# NIXIE_Display.net
KiCad netlist of a schematic drawn in Altium Designer
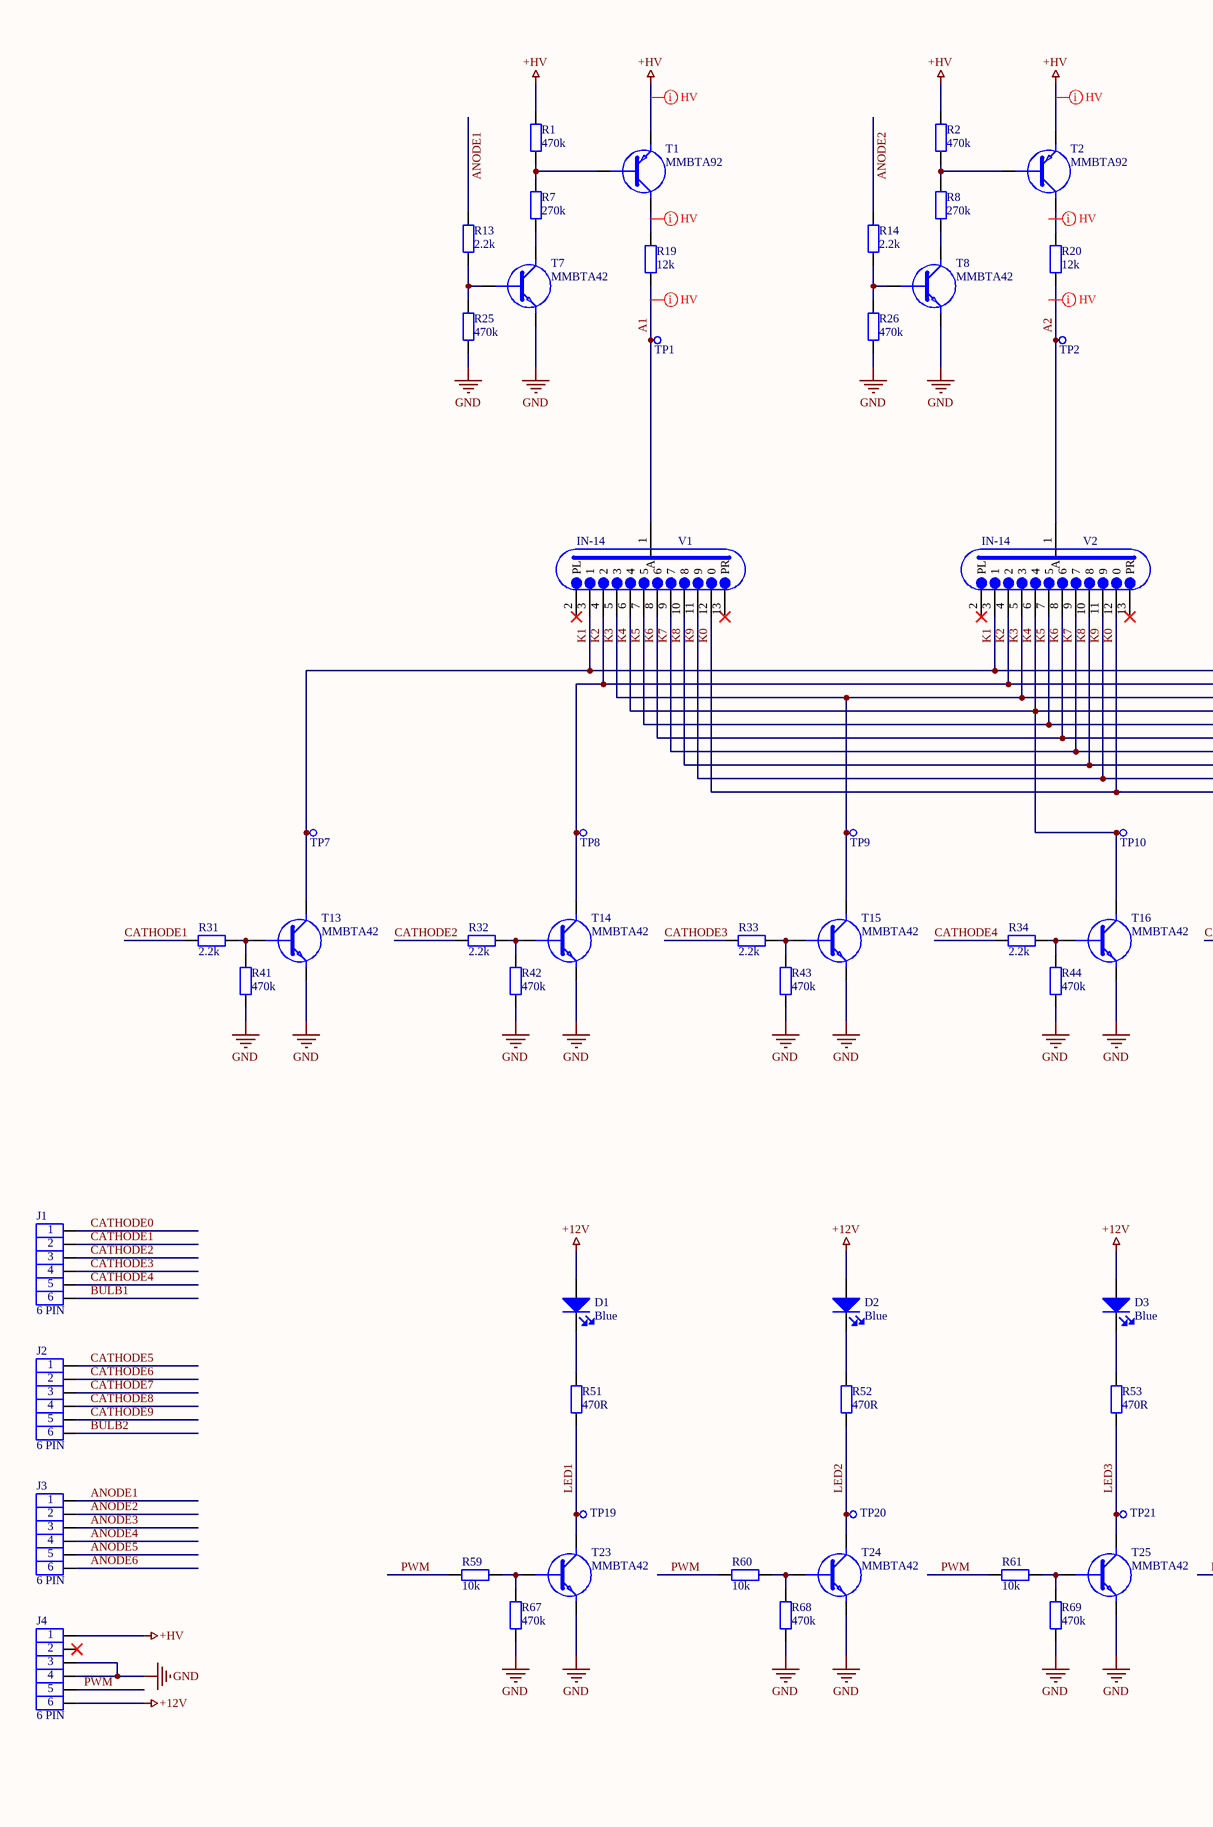
[diagram p0: NIXIE_Display.SchDoc, left]
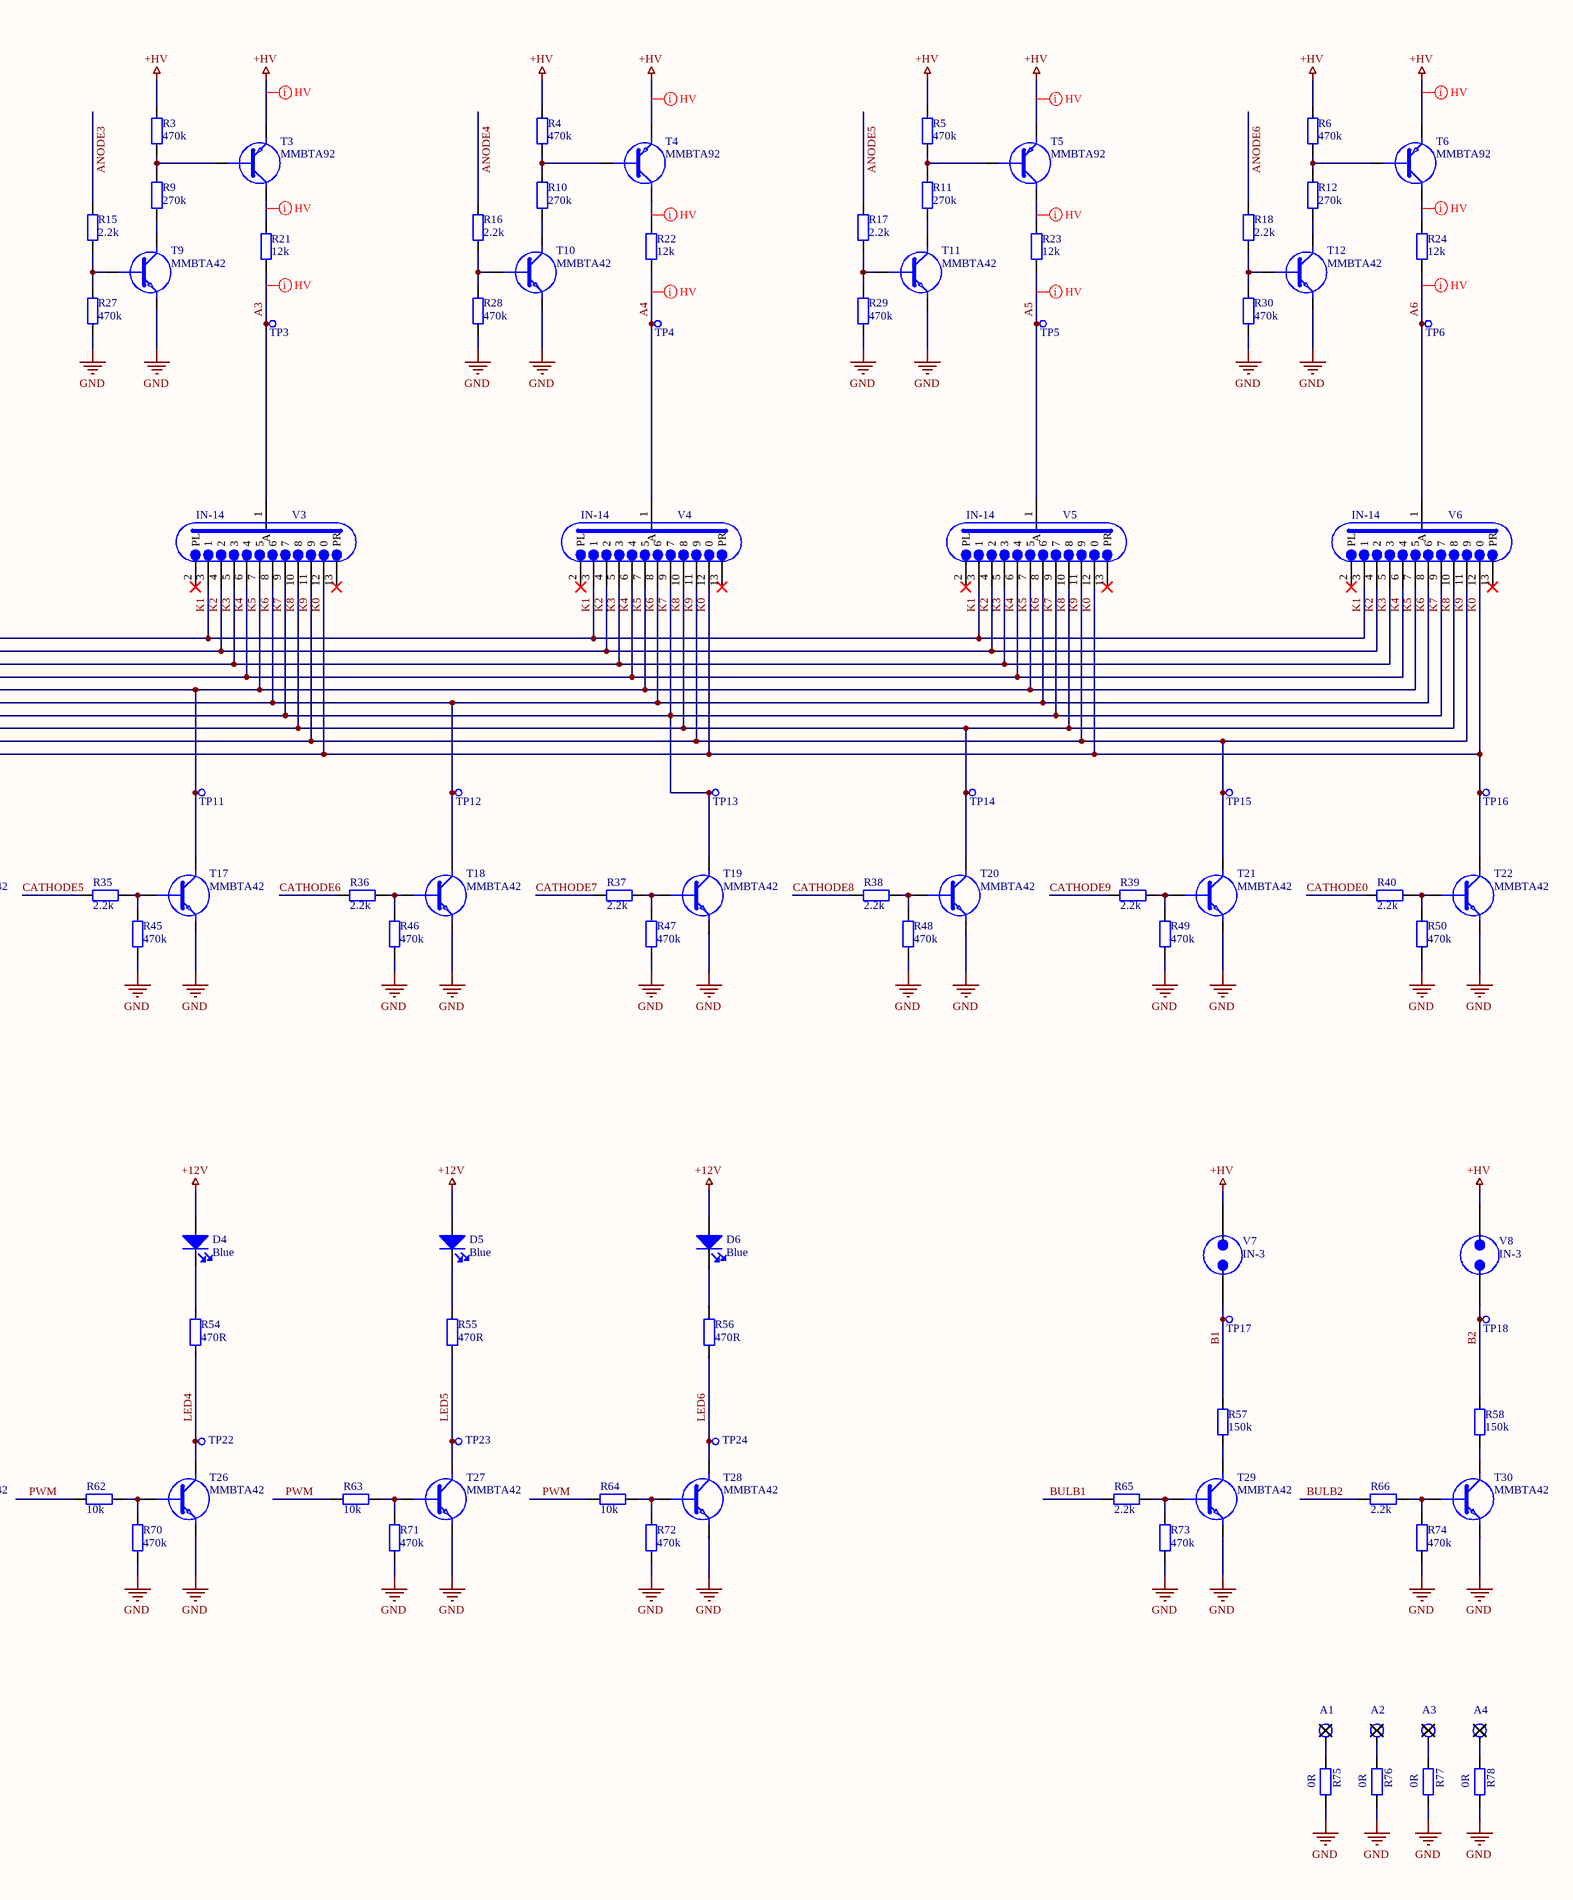
[diagram p1: NIXIE_Display.SchDoc, right]

(export (version "E")
  (design (tool "Eeschema 10.0.6"))
  (components
    (comp (ref "A1")
      (value "3mm")
      (footprint "FOOTPRINTS:HOLE M3")
      (description "Mechanical M3 Hole")
      (libsource (lib "SYMBOLS") (part "Mechanical M3 Hole"))
    )
    (comp (ref "A2")
      (value "3mm")
      (footprint "FOOTPRINTS:HOLE M3")
      (description "Mechanical M3 Hole")
      (libsource (lib "SYMBOLS") (part "Mechanical M3 Hole"))
    )
    (comp (ref "A3")
      (value "3mm")
      (footprint "FOOTPRINTS:HOLE M3")
      (description "Mechanical M3 Hole")
      (libsource (lib "SYMBOLS") (part "Mechanical M3 Hole"))
    )
    (comp (ref "A4")
      (value "3mm")
      (footprint "FOOTPRINTS:HOLE M3")
      (description "Mechanical M3 Hole")
      (libsource (lib "SYMBOLS") (part "Mechanical M3 Hole"))
    )
    (comp (ref "D1")
      (value "Blue")
      (footprint "FOOTPRINTS:LED 0805")
      (description "Standard LEDs - SMD WL-SMCW SMDMono TpVw Waterclr 0805 Blue")
      (fields
        (field (name "MANUFACTURER") "Wurth Elektronik")
        (field (name "MANUFACTURER PART NUMBER") "150080BS75000")
      )
      (libsource (lib "SYMBOLS") (part "Diode LED Blue 0805 SMD 20mA"))
    )
    (comp (ref "D2")
      (value "Blue")
      (footprint "FOOTPRINTS:LED 0805")
      (description "Standard LEDs - SMD WL-SMCW SMDMono TpVw Waterclr 0805 Blue")
      (fields
        (field (name "MANUFACTURER") "Wurth Elektronik")
        (field (name "MANUFACTURER PART NUMBER") "150080BS75000")
      )
      (libsource (lib "SYMBOLS") (part "Diode LED Blue 0805 SMD 20mA"))
    )
    (comp (ref "D3")
      (value "Blue")
      (footprint "FOOTPRINTS:LED 0805")
      (description "Standard LEDs - SMD WL-SMCW SMDMono TpVw Waterclr 0805 Blue")
      (fields
        (field (name "MANUFACTURER") "Wurth Elektronik")
        (field (name "MANUFACTURER PART NUMBER") "150080BS75000")
      )
      (libsource (lib "SYMBOLS") (part "Diode LED Blue 0805 SMD 20mA"))
    )
    (comp (ref "D4")
      (value "Blue")
      (footprint "FOOTPRINTS:LED 0805")
      (description "Standard LEDs - SMD WL-SMCW SMDMono TpVw Waterclr 0805 Blue")
      (fields
        (field (name "MANUFACTURER") "Wurth Elektronik")
        (field (name "MANUFACTURER PART NUMBER") "150080BS75000")
      )
      (libsource (lib "SYMBOLS") (part "Diode LED Blue 0805 SMD 20mA"))
    )
    (comp (ref "D5")
      (value "Blue")
      (footprint "FOOTPRINTS:LED 0805")
      (description "Standard LEDs - SMD WL-SMCW SMDMono TpVw Waterclr 0805 Blue")
      (fields
        (field (name "MANUFACTURER") "Wurth Elektronik")
        (field (name "MANUFACTURER PART NUMBER") "150080BS75000")
      )
      (libsource (lib "SYMBOLS") (part "Diode LED Blue 0805 SMD 20mA"))
    )
    (comp (ref "D6")
      (value "Blue")
      (footprint "FOOTPRINTS:LED 0805")
      (description "Standard LEDs - SMD WL-SMCW SMDMono TpVw Waterclr 0805 Blue")
      (fields
        (field (name "MANUFACTURER") "Wurth Elektronik")
        (field (name "MANUFACTURER PART NUMBER") "150080BS75000")
      )
      (libsource (lib "SYMBOLS") (part "Diode LED Blue 0805 SMD 20mA"))
    )
    (comp (ref "J1")
      (value "6 PIN")
      (footprint "FOOTPRINTS:MECHANICAL PINHEADER 6P 2.54MM MALE")
      (description "Headers & Wire Housings 2.54MM CGRIDIII HDR 6P VERT SR SEL AU")
      (fields (field (name "MANUFACTURER") "Molex") (field (name "MANUFACTURER PART NUMBER") "90120-0766"))
      (libsource (lib "SYMBOLS") (part "Mechanical Pinheader Male 6pin P=2.54mm THT"))
    )
    (comp (ref "J2")
      (value "6 PIN")
      (footprint "FOOTPRINTS:MECHANICAL PINHEADER 6P 2.54MM MALE")
      (description "Headers & Wire Housings 2.54MM CGRIDIII HDR 6P VERT SR SEL AU")
      (fields (field (name "MANUFACTURER") "Molex") (field (name "MANUFACTURER PART NUMBER") "90120-0766"))
      (libsource (lib "SYMBOLS") (part "Mechanical Pinheader Male 6pin P=2.54mm THT"))
    )
    (comp (ref "J3")
      (value "6 PIN")
      (footprint "FOOTPRINTS:MECHANICAL PINHEADER 6P 2.54MM MALE")
      (description "Headers & Wire Housings 2.54MM CGRIDIII HDR 6P VERT SR SEL AU")
      (fields (field (name "MANUFACTURER") "Molex") (field (name "MANUFACTURER PART NUMBER") "90120-0766"))
      (libsource (lib "SYMBOLS") (part "Mechanical Pinheader Male 6pin P=2.54mm THT"))
    )
    (comp (ref "J4")
      (value "6 PIN")
      (footprint "FOOTPRINTS:MECHANICAL PINHEADER 6P 2.54MM MALE")
      (description "Headers & Wire Housings 2.54MM CGRIDIII HDR 6P VERT SR SEL AU")
      (fields (field (name "MANUFACTURER") "Molex") (field (name "MANUFACTURER PART NUMBER") "90120-0766"))
      (libsource (lib "SYMBOLS") (part "Mechanical Pinheader Male 6pin P=2.54mm THT"))
    )
    (comp (ref "R1")
      (value "470k")
      (footprint "FOOTPRINTS:RESISTOR 1206")
      (description "Thin Film Resistors - SMD 1/4W470 kohm 1% 50ppm")
      (fields
        (field (name "MANUFACTURER") "Yageo")
        (field (name "MANUFACTURER PART NUMBER") "RT1206FRE07470KL")
      )
      (libsource (lib "SYMBOLS") (part "Resistor 470k 1% 1/4W 1206"))
    )
    (comp (ref "R2")
      (value "470k")
      (footprint "FOOTPRINTS:RESISTOR 1206")
      (description "Thin Film Resistors - SMD 1/4W470 kohm 1% 50ppm")
      (fields
        (field (name "MANUFACTURER") "Yageo")
        (field (name "MANUFACTURER PART NUMBER") "RT1206FRE07470KL")
      )
      (libsource (lib "SYMBOLS") (part "Resistor 470k 1% 1/4W 1206"))
    )
    (comp (ref "R3")
      (value "470k")
      (footprint "FOOTPRINTS:RESISTOR 1206")
      (description "Thin Film Resistors - SMD 1/4W470 kohm 1% 50ppm")
      (fields
        (field (name "MANUFACTURER") "Yageo")
        (field (name "MANUFACTURER PART NUMBER") "RT1206FRE07470KL")
      )
      (libsource (lib "SYMBOLS") (part "Resistor 470k 1% 1/4W 1206"))
    )
    (comp (ref "R4")
      (value "470k")
      (footprint "FOOTPRINTS:RESISTOR 1206")
      (description "Thin Film Resistors - SMD 1/4W470 kohm 1% 50ppm")
      (fields
        (field (name "MANUFACTURER") "Yageo")
        (field (name "MANUFACTURER PART NUMBER") "RT1206FRE07470KL")
      )
      (libsource (lib "SYMBOLS") (part "Resistor 470k 1% 1/4W 1206"))
    )
    (comp (ref "R5")
      (value "470k")
      (footprint "FOOTPRINTS:RESISTOR 1206")
      (description "Thin Film Resistors - SMD 1/4W470 kohm 1% 50ppm")
      (fields
        (field (name "MANUFACTURER") "Yageo")
        (field (name "MANUFACTURER PART NUMBER") "RT1206FRE07470KL")
      )
      (libsource (lib "SYMBOLS") (part "Resistor 470k 1% 1/4W 1206"))
    )
    (comp (ref "R6")
      (value "470k")
      (footprint "FOOTPRINTS:RESISTOR 1206")
      (description "Thin Film Resistors - SMD 1/4W470 kohm 1% 50ppm")
      (fields
        (field (name "MANUFACTURER") "Yageo")
        (field (name "MANUFACTURER PART NUMBER") "RT1206FRE07470KL")
      )
      (libsource (lib "SYMBOLS") (part "Resistor 470k 1% 1/4W 1206"))
    )
    (comp (ref "R7")
      (value "270k")
      (footprint "FOOTPRINTS:RESISTOR 1206")
      (description "Thin Film Resistors - SMD 1/4W 270 kohm 1% 50ppm")
      (fields
        (field (name "MANUFACTURER") "Yageo")
        (field (name "MANUFACTURER PART NUMBER") "RT1206FRE07270KL")
      )
      (libsource (lib "SYMBOLS") (part "Resistor 270k 1% 1/4W 1206"))
    )
    (comp (ref "R8")
      (value "270k")
      (footprint "FOOTPRINTS:RESISTOR 1206")
      (description "Thin Film Resistors - SMD 1/4W 270 kohm 1% 50ppm")
      (fields
        (field (name "MANUFACTURER") "Yageo")
        (field (name "MANUFACTURER PART NUMBER") "RT1206FRE07270KL")
      )
      (libsource (lib "SYMBOLS") (part "Resistor 270k 1% 1/4W 1206"))
    )
    (comp (ref "R9")
      (value "270k")
      (footprint "FOOTPRINTS:RESISTOR 1206")
      (description "Thin Film Resistors - SMD 1/4W 270 kohm 1% 50ppm")
      (fields
        (field (name "MANUFACTURER") "Yageo")
        (field (name "MANUFACTURER PART NUMBER") "RT1206FRE07270KL")
      )
      (libsource (lib "SYMBOLS") (part "Resistor 270k 1% 1/4W 1206"))
    )
    (comp (ref "R10")
      (value "270k")
      (footprint "FOOTPRINTS:RESISTOR 1206")
      (description "Thin Film Resistors - SMD 1/4W 270 kohm 1% 50ppm")
      (fields
        (field (name "MANUFACTURER") "Yageo")
        (field (name "MANUFACTURER PART NUMBER") "RT1206FRE07270KL")
      )
      (libsource (lib "SYMBOLS") (part "Resistor 270k 1% 1/4W 1206"))
    )
    (comp (ref "R11")
      (value "270k")
      (footprint "FOOTPRINTS:RESISTOR 1206")
      (description "Thin Film Resistors - SMD 1/4W 270 kohm 1% 50ppm")
      (fields
        (field (name "MANUFACTURER") "Yageo")
        (field (name "MANUFACTURER PART NUMBER") "RT1206FRE07270KL")
      )
      (libsource (lib "SYMBOLS") (part "Resistor 270k 1% 1/4W 1206"))
    )
    (comp (ref "R12")
      (value "270k")
      (footprint "FOOTPRINTS:RESISTOR 1206")
      (description "Thin Film Resistors - SMD 1/4W 270 kohm 1% 50ppm")
      (fields
        (field (name "MANUFACTURER") "Yageo")
        (field (name "MANUFACTURER PART NUMBER") "RT1206FRE07270KL")
      )
      (libsource (lib "SYMBOLS") (part "Resistor 270k 1% 1/4W 1206"))
    )
    (comp (ref "R13")
      (value "2.2k")
      (footprint "FOOTPRINTS:RESISTOR 0603")
      (description "Thin Film Resistors - SMD 1/10W 2.2K ohm 1% 50ppm")
      (fields
        (field (name "MANUFACTURER") "Yageo")
        (field (name "MANUFACTURER PART NUMBER") "RT0603FRE072K2L")
      )
      (libsource (lib "SYMBOLS") (part "Resistor 2.2k 1% 1/10W 0603"))
    )
    (comp (ref "R14")
      (value "2.2k")
      (footprint "FOOTPRINTS:RESISTOR 0603")
      (description "Thin Film Resistors - SMD 1/10W 2.2K ohm 1% 50ppm")
      (fields
        (field (name "MANUFACTURER") "Yageo")
        (field (name "MANUFACTURER PART NUMBER") "RT0603FRE072K2L")
      )
      (libsource (lib "SYMBOLS") (part "Resistor 2.2k 1% 1/10W 0603"))
    )
    (comp (ref "R15")
      (value "2.2k")
      (footprint "FOOTPRINTS:RESISTOR 0603")
      (description "Thin Film Resistors - SMD 1/10W 2.2K ohm 1% 50ppm")
      (fields
        (field (name "MANUFACTURER") "Yageo")
        (field (name "MANUFACTURER PART NUMBER") "RT0603FRE072K2L")
      )
      (libsource (lib "SYMBOLS") (part "Resistor 2.2k 1% 1/10W 0603"))
    )
    (comp (ref "R16")
      (value "2.2k")
      (footprint "FOOTPRINTS:RESISTOR 0603")
      (description "Thin Film Resistors - SMD 1/10W 2.2K ohm 1% 50ppm")
      (fields
        (field (name "MANUFACTURER") "Yageo")
        (field (name "MANUFACTURER PART NUMBER") "RT0603FRE072K2L")
      )
      (libsource (lib "SYMBOLS") (part "Resistor 2.2k 1% 1/10W 0603"))
    )
    (comp (ref "R17")
      (value "2.2k")
      (footprint "FOOTPRINTS:RESISTOR 0603")
      (description "Thin Film Resistors - SMD 1/10W 2.2K ohm 1% 50ppm")
      (fields
        (field (name "MANUFACTURER") "Yageo")
        (field (name "MANUFACTURER PART NUMBER") "RT0603FRE072K2L")
      )
      (libsource (lib "SYMBOLS") (part "Resistor 2.2k 1% 1/10W 0603"))
    )
    (comp (ref "R18")
      (value "2.2k")
      (footprint "FOOTPRINTS:RESISTOR 0603")
      (description "Thin Film Resistors - SMD 1/10W 2.2K ohm 1% 50ppm")
      (fields
        (field (name "MANUFACTURER") "Yageo")
        (field (name "MANUFACTURER PART NUMBER") "RT0603FRE072K2L")
      )
      (libsource (lib "SYMBOLS") (part "Resistor 2.2k 1% 1/10W 0603"))
    )
    (comp (ref "R19")
      (value "12k")
      (footprint "FOOTPRINTS:RESISTOR 0603")
      (description "Thin Film Resistors - SMD 1/10W 12K ohm 1% 50ppm")
      (fields
        (field (name "MANUFACTURER") "Yageo")
        (field (name "MANUFACTURER PART NUMBER") "RT0603FRE1312KL")
      )
      (libsource (lib "SYMBOLS") (part "Resistor 12k 1% 1/10W 0603"))
    )
    (comp (ref "R20")
      (value "12k")
      (footprint "FOOTPRINTS:RESISTOR 0603")
      (description "Thin Film Resistors - SMD 1/10W 12K ohm 1% 50ppm")
      (fields
        (field (name "MANUFACTURER") "Yageo")
        (field (name "MANUFACTURER PART NUMBER") "RT0603FRE1312KL")
      )
      (libsource (lib "SYMBOLS") (part "Resistor 12k 1% 1/10W 0603"))
    )
    (comp (ref "R21")
      (value "12k")
      (footprint "FOOTPRINTS:RESISTOR 0603")
      (description "Thin Film Resistors - SMD 1/10W 12K ohm 1% 50ppm")
      (fields
        (field (name "MANUFACTURER") "Yageo")
        (field (name "MANUFACTURER PART NUMBER") "RT0603FRE1312KL")
      )
      (libsource (lib "SYMBOLS") (part "Resistor 12k 1% 1/10W 0603"))
    )
    (comp (ref "R22")
      (value "12k")
      (footprint "FOOTPRINTS:RESISTOR 0603")
      (description "Thin Film Resistors - SMD 1/10W 12K ohm 1% 50ppm")
      (fields
        (field (name "MANUFACTURER") "Yageo")
        (field (name "MANUFACTURER PART NUMBER") "RT0603FRE1312KL")
      )
      (libsource (lib "SYMBOLS") (part "Resistor 12k 1% 1/10W 0603"))
    )
    (comp (ref "R23")
      (value "12k")
      (footprint "FOOTPRINTS:RESISTOR 0603")
      (description "Thin Film Resistors - SMD 1/10W 12K ohm 1% 50ppm")
      (fields
        (field (name "MANUFACTURER") "Yageo")
        (field (name "MANUFACTURER PART NUMBER") "RT0603FRE1312KL")
      )
      (libsource (lib "SYMBOLS") (part "Resistor 12k 1% 1/10W 0603"))
    )
    (comp (ref "R24")
      (value "12k")
      (footprint "FOOTPRINTS:RESISTOR 0603")
      (description "Thin Film Resistors - SMD 1/10W 12K ohm 1% 50ppm")
      (fields
        (field (name "MANUFACTURER") "Yageo")
        (field (name "MANUFACTURER PART NUMBER") "RT0603FRE1312KL")
      )
      (libsource (lib "SYMBOLS") (part "Resistor 12k 1% 1/10W 0603"))
    )
    (comp (ref "R25")
      (value "470k")
      (footprint "FOOTPRINTS:RESISTOR 0603")
      (description "Thin Film Resistors - SMD 1/10W 470K ohm 1% 50ppm")
      (fields
        (field (name "MANUFACTURER") "Yageo")
        (field (name "MANUFACTURER PART NUMBER") "RT0603FRE13470KL")
      )
      (libsource (lib "SYMBOLS") (part "Resistor 470k 1% 1/10W 0603"))
    )
    (comp (ref "R26")
      (value "470k")
      (footprint "FOOTPRINTS:RESISTOR 0603")
      (description "Thin Film Resistors - SMD 1/10W 470K ohm 1% 50ppm")
      (fields
        (field (name "MANUFACTURER") "Yageo")
        (field (name "MANUFACTURER PART NUMBER") "RT0603FRE13470KL")
      )
      (libsource (lib "SYMBOLS") (part "Resistor 470k 1% 1/10W 0603"))
    )
    (comp (ref "R27")
      (value "470k")
      (footprint "FOOTPRINTS:RESISTOR 0603")
      (description "Thin Film Resistors - SMD 1/10W 470K ohm 1% 50ppm")
      (fields
        (field (name "MANUFACTURER") "Yageo")
        (field (name "MANUFACTURER PART NUMBER") "RT0603FRE13470KL")
      )
      (libsource (lib "SYMBOLS") (part "Resistor 470k 1% 1/10W 0603"))
    )
    (comp (ref "R28")
      (value "470k")
      (footprint "FOOTPRINTS:RESISTOR 0603")
      (description "Thin Film Resistors - SMD 1/10W 470K ohm 1% 50ppm")
      (fields
        (field (name "MANUFACTURER") "Yageo")
        (field (name "MANUFACTURER PART NUMBER") "RT0603FRE13470KL")
      )
      (libsource (lib "SYMBOLS") (part "Resistor 470k 1% 1/10W 0603"))
    )
    (comp (ref "R29")
      (value "470k")
      (footprint "FOOTPRINTS:RESISTOR 0603")
      (description "Thin Film Resistors - SMD 1/10W 470K ohm 1% 50ppm")
      (fields
        (field (name "MANUFACTURER") "Yageo")
        (field (name "MANUFACTURER PART NUMBER") "RT0603FRE13470KL")
      )
      (libsource (lib "SYMBOLS") (part "Resistor 470k 1% 1/10W 0603"))
    )
    (comp (ref "R30")
      (value "470k")
      (footprint "FOOTPRINTS:RESISTOR 0603")
      (description "Thin Film Resistors - SMD 1/10W 470K ohm 1% 50ppm")
      (fields
        (field (name "MANUFACTURER") "Yageo")
        (field (name "MANUFACTURER PART NUMBER") "RT0603FRE13470KL")
      )
      (libsource (lib "SYMBOLS") (part "Resistor 470k 1% 1/10W 0603"))
    )
    (comp (ref "R31")
      (value "2.2k")
      (footprint "FOOTPRINTS:RESISTOR 0603")
      (description "Thin Film Resistors - SMD 1/10W 2.2K ohm 1% 50ppm")
      (fields
        (field (name "MANUFACTURER") "Yageo")
        (field (name "MANUFACTURER PART NUMBER") "RT0603FRE072K2L")
      )
      (libsource (lib "") (part "Resistor 2.2k 1% 1/10W 0603_1"))
    )
    (comp (ref "R32")
      (value "2.2k")
      (footprint "FOOTPRINTS:RESISTOR 0603")
      (description "Thin Film Resistors - SMD 1/10W 2.2K ohm 1% 50ppm")
      (fields
        (field (name "MANUFACTURER") "Yageo")
        (field (name "MANUFACTURER PART NUMBER") "RT0603FRE072K2L")
      )
      (libsource (lib "") (part "Resistor 2.2k 1% 1/10W 0603_1"))
    )
    (comp (ref "R33")
      (value "2.2k")
      (footprint "FOOTPRINTS:RESISTOR 0603")
      (description "Thin Film Resistors - SMD 1/10W 2.2K ohm 1% 50ppm")
      (fields
        (field (name "MANUFACTURER") "Yageo")
        (field (name "MANUFACTURER PART NUMBER") "RT0603FRE072K2L")
      )
      (libsource (lib "") (part "Resistor 2.2k 1% 1/10W 0603_1"))
    )
    (comp (ref "R34")
      (value "2.2k")
      (footprint "FOOTPRINTS:RESISTOR 0603")
      (description "Thin Film Resistors - SMD 1/10W 2.2K ohm 1% 50ppm")
      (fields
        (field (name "MANUFACTURER") "Yageo")
        (field (name "MANUFACTURER PART NUMBER") "RT0603FRE072K2L")
      )
      (libsource (lib "") (part "Resistor 2.2k 1% 1/10W 0603_1"))
    )
    (comp (ref "R35")
      (value "2.2k")
      (footprint "FOOTPRINTS:RESISTOR 0603")
      (description "Thin Film Resistors - SMD 1/10W 2.2K ohm 1% 50ppm")
      (fields
        (field (name "MANUFACTURER") "Yageo")
        (field (name "MANUFACTURER PART NUMBER") "RT0603FRE072K2L")
      )
      (libsource (lib "") (part "Resistor 2.2k 1% 1/10W 0603_1"))
    )
    (comp (ref "R36")
      (value "2.2k")
      (footprint "FOOTPRINTS:RESISTOR 0603")
      (description "Thin Film Resistors - SMD 1/10W 2.2K ohm 1% 50ppm")
      (fields
        (field (name "MANUFACTURER") "Yageo")
        (field (name "MANUFACTURER PART NUMBER") "RT0603FRE072K2L")
      )
      (libsource (lib "") (part "Resistor 2.2k 1% 1/10W 0603_1"))
    )
    (comp (ref "R37")
      (value "2.2k")
      (footprint "FOOTPRINTS:RESISTOR 0603")
      (description "Thin Film Resistors - SMD 1/10W 2.2K ohm 1% 50ppm")
      (fields
        (field (name "MANUFACTURER") "Yageo")
        (field (name "MANUFACTURER PART NUMBER") "RT0603FRE072K2L")
      )
      (libsource (lib "") (part "Resistor 2.2k 1% 1/10W 0603_1"))
    )
    (comp (ref "R38")
      (value "2.2k")
      (footprint "FOOTPRINTS:RESISTOR 0603")
      (description "Thin Film Resistors - SMD 1/10W 2.2K ohm 1% 50ppm")
      (fields
        (field (name "MANUFACTURER") "Yageo")
        (field (name "MANUFACTURER PART NUMBER") "RT0603FRE072K2L")
      )
      (libsource (lib "") (part "Resistor 2.2k 1% 1/10W 0603_1"))
    )
    (comp (ref "R39")
      (value "2.2k")
      (footprint "FOOTPRINTS:RESISTOR 0603")
      (description "Thin Film Resistors - SMD 1/10W 2.2K ohm 1% 50ppm")
      (fields
        (field (name "MANUFACTURER") "Yageo")
        (field (name "MANUFACTURER PART NUMBER") "RT0603FRE072K2L")
      )
      (libsource (lib "") (part "Resistor 2.2k 1% 1/10W 0603_1"))
    )
    (comp (ref "R40")
      (value "2.2k")
      (footprint "FOOTPRINTS:RESISTOR 0603")
      (description "Thin Film Resistors - SMD 1/10W 2.2K ohm 1% 50ppm")
      (fields
        (field (name "MANUFACTURER") "Yageo")
        (field (name "MANUFACTURER PART NUMBER") "RT0603FRE072K2L")
      )
      (libsource (lib "") (part "Resistor 2.2k 1% 1/10W 0603_1"))
    )
    (comp (ref "R41")
      (value "470k")
      (footprint "FOOTPRINTS:RESISTOR 0603")
      (description "Thin Film Resistors - SMD 1/10W 470K ohm 1% 50ppm")
      (fields
        (field (name "MANUFACTURER") "Yageo")
        (field (name "MANUFACTURER PART NUMBER") "RT0603FRE13470KL")
      )
      (libsource (lib "SYMBOLS") (part "Resistor 470k 1% 1/10W 0603"))
    )
    (comp (ref "R42")
      (value "470k")
      (footprint "FOOTPRINTS:RESISTOR 0603")
      (description "Thin Film Resistors - SMD 1/10W 470K ohm 1% 50ppm")
      (fields
        (field (name "MANUFACTURER") "Yageo")
        (field (name "MANUFACTURER PART NUMBER") "RT0603FRE13470KL")
      )
      (libsource (lib "SYMBOLS") (part "Resistor 470k 1% 1/10W 0603"))
    )
    (comp (ref "R43")
      (value "470k")
      (footprint "FOOTPRINTS:RESISTOR 0603")
      (description "Thin Film Resistors - SMD 1/10W 470K ohm 1% 50ppm")
      (fields
        (field (name "MANUFACTURER") "Yageo")
        (field (name "MANUFACTURER PART NUMBER") "RT0603FRE13470KL")
      )
      (libsource (lib "SYMBOLS") (part "Resistor 470k 1% 1/10W 0603"))
    )
    (comp (ref "R44")
      (value "470k")
      (footprint "FOOTPRINTS:RESISTOR 0603")
      (description "Thin Film Resistors - SMD 1/10W 470K ohm 1% 50ppm")
      (fields
        (field (name "MANUFACTURER") "Yageo")
        (field (name "MANUFACTURER PART NUMBER") "RT0603FRE13470KL")
      )
      (libsource (lib "SYMBOLS") (part "Resistor 470k 1% 1/10W 0603"))
    )
    (comp (ref "R45")
      (value "470k")
      (footprint "FOOTPRINTS:RESISTOR 0603")
      (description "Thin Film Resistors - SMD 1/10W 470K ohm 1% 50ppm")
      (fields
        (field (name "MANUFACTURER") "Yageo")
        (field (name "MANUFACTURER PART NUMBER") "RT0603FRE13470KL")
      )
      (libsource (lib "SYMBOLS") (part "Resistor 470k 1% 1/10W 0603"))
    )
    (comp (ref "R46")
      (value "470k")
      (footprint "FOOTPRINTS:RESISTOR 0603")
      (description "Thin Film Resistors - SMD 1/10W 470K ohm 1% 50ppm")
      (fields
        (field (name "MANUFACTURER") "Yageo")
        (field (name "MANUFACTURER PART NUMBER") "RT0603FRE13470KL")
      )
      (libsource (lib "SYMBOLS") (part "Resistor 470k 1% 1/10W 0603"))
    )
    (comp (ref "R47")
      (value "470k")
      (footprint "FOOTPRINTS:RESISTOR 0603")
      (description "Thin Film Resistors - SMD 1/10W 470K ohm 1% 50ppm")
      (fields
        (field (name "MANUFACTURER") "Yageo")
        (field (name "MANUFACTURER PART NUMBER") "RT0603FRE13470KL")
      )
      (libsource (lib "SYMBOLS") (part "Resistor 470k 1% 1/10W 0603"))
    )
    (comp (ref "R48")
      (value "470k")
      (footprint "FOOTPRINTS:RESISTOR 0603")
      (description "Thin Film Resistors - SMD 1/10W 470K ohm 1% 50ppm")
      (fields
        (field (name "MANUFACTURER") "Yageo")
        (field (name "MANUFACTURER PART NUMBER") "RT0603FRE13470KL")
      )
      (libsource (lib "SYMBOLS") (part "Resistor 470k 1% 1/10W 0603"))
    )
    (comp (ref "R49")
      (value "470k")
      (footprint "FOOTPRINTS:RESISTOR 0603")
      (description "Thin Film Resistors - SMD 1/10W 470K ohm 1% 50ppm")
      (fields
        (field (name "MANUFACTURER") "Yageo")
        (field (name "MANUFACTURER PART NUMBER") "RT0603FRE13470KL")
      )
      (libsource (lib "SYMBOLS") (part "Resistor 470k 1% 1/10W 0603"))
    )
    (comp (ref "R50")
      (value "470k")
      (footprint "FOOTPRINTS:RESISTOR 0603")
      (description "Thin Film Resistors - SMD 1/10W 470K ohm 1% 50ppm")
      (fields
        (field (name "MANUFACTURER") "Yageo")
        (field (name "MANUFACTURER PART NUMBER") "RT0603FRE13470KL")
      )
      (libsource (lib "SYMBOLS") (part "Resistor 470k 1% 1/10W 0603"))
    )
    (comp (ref "R51")
      (value "470R")
      (footprint "FOOTPRINTS:RESISTOR 0603")
      (description "Thin Film Resistors - SMD 1/10W 470R ohm 1% 50ppm")
      (fields
        (field (name "MANUFACTURER") "Yageo")
        (field (name "MANUFACTURER PART NUMBER") "RT0603FRE07470RL")
      )
      (libsource (lib "SYMBOLS") (part "Resistor 470R 1% 1/10W 0603"))
    )
    (comp (ref "R52")
      (value "470R")
      (footprint "FOOTPRINTS:RESISTOR 0603")
      (description "Thin Film Resistors - SMD 1/10W 470R ohm 1% 50ppm")
      (fields
        (field (name "MANUFACTURER") "Yageo")
        (field (name "MANUFACTURER PART NUMBER") "RT0603FRE07470RL")
      )
      (libsource (lib "SYMBOLS") (part "Resistor 470R 1% 1/10W 0603"))
    )
    (comp (ref "R53")
      (value "470R")
      (footprint "FOOTPRINTS:RESISTOR 0603")
      (description "Thin Film Resistors - SMD 1/10W 470R ohm 1% 50ppm")
      (fields
        (field (name "MANUFACTURER") "Yageo")
        (field (name "MANUFACTURER PART NUMBER") "RT0603FRE07470RL")
      )
      (libsource (lib "SYMBOLS") (part "Resistor 470R 1% 1/10W 0603"))
    )
    (comp (ref "R54")
      (value "470R")
      (footprint "FOOTPRINTS:RESISTOR 0603")
      (description "Thin Film Resistors - SMD 1/10W 470R ohm 1% 50ppm")
      (fields
        (field (name "MANUFACTURER") "Yageo")
        (field (name "MANUFACTURER PART NUMBER") "RT0603FRE07470RL")
      )
      (libsource (lib "SYMBOLS") (part "Resistor 470R 1% 1/10W 0603"))
    )
    (comp (ref "R55")
      (value "470R")
      (footprint "FOOTPRINTS:RESISTOR 0603")
      (description "Thin Film Resistors - SMD 1/10W 470R ohm 1% 50ppm")
      (fields
        (field (name "MANUFACTURER") "Yageo")
        (field (name "MANUFACTURER PART NUMBER") "RT0603FRE07470RL")
      )
      (libsource (lib "SYMBOLS") (part "Resistor 470R 1% 1/10W 0603"))
    )
    (comp (ref "R56")
      (value "470R")
      (footprint "FOOTPRINTS:RESISTOR 0603")
      (description "Thin Film Resistors - SMD 1/10W 470R ohm 1% 50ppm")
      (fields
        (field (name "MANUFACTURER") "Yageo")
        (field (name "MANUFACTURER PART NUMBER") "RT0603FRE07470RL")
      )
      (libsource (lib "SYMBOLS") (part "Resistor 470R 1% 1/10W 0603"))
    )
    (comp (ref "R57")
      (value "150k")
      (footprint "FOOTPRINTS:RESISTOR 0603")
      (description "Thin Film Resistors - SMD 1/10W 150K ohm 1% 50ppm")
      (fields
        (field (name "MANUFACTURER") "Yageo")
        (field (name "MANUFACTURER PART NUMBER") "RT0603FRE13150KL")
      )
      (libsource (lib "SYMBOLS") (part "Resistor 150k 1% 1/10W 0603"))
    )
    (comp (ref "R58")
      (value "150k")
      (footprint "FOOTPRINTS:RESISTOR 0603")
      (description "Thin Film Resistors - SMD 1/10W 150K ohm 1% 50ppm")
      (fields
        (field (name "MANUFACTURER") "Yageo")
        (field (name "MANUFACTURER PART NUMBER") "RT0603FRE13150KL")
      )
      (libsource (lib "SYMBOLS") (part "Resistor 150k 1% 1/10W 0603"))
    )
    (comp (ref "R59")
      (value "10k")
      (footprint "FOOTPRINTS:RESISTOR 0603")
      (description "Thin Film Resistors - SMD 1/10W 10K ohm 1% 50ppm")
      (fields
        (field (name "MANUFACTURER") "Yageo")
        (field (name "MANUFACTURER PART NUMBER") "RT0603FRE1310KL")
      )
      (libsource (lib "SYMBOLS") (part "Resistor 10k 1% 1/10W 0603"))
    )
    (comp (ref "R60")
      (value "10k")
      (footprint "FOOTPRINTS:RESISTOR 0603")
      (description "Thin Film Resistors - SMD 1/10W 10K ohm 1% 50ppm")
      (fields
        (field (name "MANUFACTURER") "Yageo")
        (field (name "MANUFACTURER PART NUMBER") "RT0603FRE1310KL")
      )
      (libsource (lib "SYMBOLS") (part "Resistor 10k 1% 1/10W 0603"))
    )
    (comp (ref "R61")
      (value "10k")
      (footprint "FOOTPRINTS:RESISTOR 0603")
      (description "Thin Film Resistors - SMD 1/10W 10K ohm 1% 50ppm")
      (fields
        (field (name "MANUFACTURER") "Yageo")
        (field (name "MANUFACTURER PART NUMBER") "RT0603FRE1310KL")
      )
      (libsource (lib "SYMBOLS") (part "Resistor 10k 1% 1/10W 0603"))
    )
    (comp (ref "R62")
      (value "10k")
      (footprint "FOOTPRINTS:RESISTOR 0603")
      (description "Thin Film Resistors - SMD 1/10W 10K ohm 1% 50ppm")
      (fields
        (field (name "MANUFACTURER") "Yageo")
        (field (name "MANUFACTURER PART NUMBER") "RT0603FRE1310KL")
      )
      (libsource (lib "SYMBOLS") (part "Resistor 10k 1% 1/10W 0603"))
    )
    (comp (ref "R63")
      (value "10k")
      (footprint "FOOTPRINTS:RESISTOR 0603")
      (description "Thin Film Resistors - SMD 1/10W 10K ohm 1% 50ppm")
      (fields
        (field (name "MANUFACTURER") "Yageo")
        (field (name "MANUFACTURER PART NUMBER") "RT0603FRE1310KL")
      )
      (libsource (lib "SYMBOLS") (part "Resistor 10k 1% 1/10W 0603"))
    )
    (comp (ref "R64")
      (value "10k")
      (footprint "FOOTPRINTS:RESISTOR 0603")
      (description "Thin Film Resistors - SMD 1/10W 10K ohm 1% 50ppm")
      (fields
        (field (name "MANUFACTURER") "Yageo")
        (field (name "MANUFACTURER PART NUMBER") "RT0603FRE1310KL")
      )
      (libsource (lib "SYMBOLS") (part "Resistor 10k 1% 1/10W 0603"))
    )
    (comp (ref "R65")
      (value "2.2k")
      (footprint "FOOTPRINTS:RESISTOR 0603")
      (description "Thin Film Resistors - SMD 1/10W 2.2K ohm 1% 50ppm")
      (fields
        (field (name "MANUFACTURER") "Yageo")
        (field (name "MANUFACTURER PART NUMBER") "RT0603FRE072K2L")
      )
      (libsource (lib "") (part "Resistor 2.2k 1% 1/10W 0603_1"))
    )
    (comp (ref "R66")
      (value "2.2k")
      (footprint "FOOTPRINTS:RESISTOR 0603")
      (description "Thin Film Resistors - SMD 1/10W 2.2K ohm 1% 50ppm")
      (fields
        (field (name "MANUFACTURER") "Yageo")
        (field (name "MANUFACTURER PART NUMBER") "RT0603FRE072K2L")
      )
      (libsource (lib "") (part "Resistor 2.2k 1% 1/10W 0603_1"))
    )
    (comp (ref "R67")
      (value "470k")
      (footprint "FOOTPRINTS:RESISTOR 0603")
      (description "Thin Film Resistors - SMD 1/10W 470K ohm 1% 50ppm")
      (fields
        (field (name "MANUFACTURER") "Yageo")
        (field (name "MANUFACTURER PART NUMBER") "RT0603FRE13470KL")
      )
      (libsource (lib "SYMBOLS") (part "Resistor 470k 1% 1/10W 0603"))
    )
    (comp (ref "R68")
      (value "470k")
      (footprint "FOOTPRINTS:RESISTOR 0603")
      (description "Thin Film Resistors - SMD 1/10W 470K ohm 1% 50ppm")
      (fields
        (field (name "MANUFACTURER") "Yageo")
        (field (name "MANUFACTURER PART NUMBER") "RT0603FRE13470KL")
      )
      (libsource (lib "SYMBOLS") (part "Resistor 470k 1% 1/10W 0603"))
    )
    (comp (ref "R69")
      (value "470k")
      (footprint "FOOTPRINTS:RESISTOR 0603")
      (description "Thin Film Resistors - SMD 1/10W 470K ohm 1% 50ppm")
      (fields
        (field (name "MANUFACTURER") "Yageo")
        (field (name "MANUFACTURER PART NUMBER") "RT0603FRE13470KL")
      )
      (libsource (lib "SYMBOLS") (part "Resistor 470k 1% 1/10W 0603"))
    )
    (comp (ref "R70")
      (value "470k")
      (footprint "FOOTPRINTS:RESISTOR 0603")
      (description "Thin Film Resistors - SMD 1/10W 470K ohm 1% 50ppm")
      (fields
        (field (name "MANUFACTURER") "Yageo")
        (field (name "MANUFACTURER PART NUMBER") "RT0603FRE13470KL")
      )
      (libsource (lib "SYMBOLS") (part "Resistor 470k 1% 1/10W 0603"))
    )
    (comp (ref "R71")
      (value "470k")
      (footprint "FOOTPRINTS:RESISTOR 0603")
      (description "Thin Film Resistors - SMD 1/10W 470K ohm 1% 50ppm")
      (fields
        (field (name "MANUFACTURER") "Yageo")
        (field (name "MANUFACTURER PART NUMBER") "RT0603FRE13470KL")
      )
      (libsource (lib "SYMBOLS") (part "Resistor 470k 1% 1/10W 0603"))
    )
    (comp (ref "R72")
      (value "470k")
      (footprint "FOOTPRINTS:RESISTOR 0603")
      (description "Thin Film Resistors - SMD 1/10W 470K ohm 1% 50ppm")
      (fields
        (field (name "MANUFACTURER") "Yageo")
        (field (name "MANUFACTURER PART NUMBER") "RT0603FRE13470KL")
      )
      (libsource (lib "SYMBOLS") (part "Resistor 470k 1% 1/10W 0603"))
    )
    (comp (ref "R73")
      (value "470k")
      (footprint "FOOTPRINTS:RESISTOR 0603")
      (description "Thin Film Resistors - SMD 1/10W 470K ohm 1% 50ppm")
      (fields
        (field (name "MANUFACTURER") "Yageo")
        (field (name "MANUFACTURER PART NUMBER") "RT0603FRE13470KL")
      )
      (libsource (lib "SYMBOLS") (part "Resistor 470k 1% 1/10W 0603"))
    )
    (comp (ref "R74")
      (value "470k")
      (footprint "FOOTPRINTS:RESISTOR 0603")
      (description "Thin Film Resistors - SMD 1/10W 470K ohm 1% 50ppm")
      (fields
        (field (name "MANUFACTURER") "Yageo")
        (field (name "MANUFACTURER PART NUMBER") "RT0603FRE13470KL")
      )
      (libsource (lib "SYMBOLS") (part "Resistor 470k 1% 1/10W 0603"))
    )
    (comp (ref "R75")
      (value "0R")
      (footprint "FOOTPRINTS:RESISTOR 0603")
      (description "Thick Film Resistors - SMD 0 Ohms 100 mW 0603 5%")
      (fields
        (field (name "MANUFACTURER") "Yageo")
        (field (name "MANUFACTURER PART NUMBER") "RC0603JR-070RL")
      )
      (libsource (lib "SYMBOLS") (part "Resistor 0R 1% 1/10W 0603"))
    )
    (comp (ref "R76")
      (value "0R")
      (footprint "FOOTPRINTS:RESISTOR 0603")
      (description "Thick Film Resistors - SMD 0 Ohms 100 mW 0603 5%")
      (fields
        (field (name "MANUFACTURER") "Yageo")
        (field (name "MANUFACTURER PART NUMBER") "RC0603JR-070RL")
      )
      (libsource (lib "SYMBOLS") (part "Resistor 0R 1% 1/10W 0603"))
    )
    (comp (ref "R77")
      (value "0R")
      (footprint "FOOTPRINTS:RESISTOR 0603")
      (description "Thick Film Resistors - SMD 0 Ohms 100 mW 0603 5%")
      (fields
        (field (name "MANUFACTURER") "Yageo")
        (field (name "MANUFACTURER PART NUMBER") "RC0603JR-070RL")
      )
      (libsource (lib "SYMBOLS") (part "Resistor 0R 1% 1/10W 0603"))
    )
    (comp (ref "R78")
      (value "0R")
      (footprint "FOOTPRINTS:RESISTOR 0603")
      (description "Thick Film Resistors - SMD 0 Ohms 100 mW 0603 5%")
      (fields
        (field (name "MANUFACTURER") "Yageo")
        (field (name "MANUFACTURER PART NUMBER") "RC0603JR-070RL")
      )
      (libsource (lib "SYMBOLS") (part "Resistor 0R 1% 1/10W 0603"))
    )
    (comp (ref "T1")
      (value "MMBTA92")
      (footprint "FOOTPRINTS:SOT23-3")
      (description "Bipolar Transistors - BJT BJT, SOT-23, 300V, 500mA, PNP")
      (fields
        (field (name "MANUFACTURER PART NUMBER") "MMBTA42")
        (field (name "MANUFACTURER") "Diotec Semiconductor")
      )
      (libsource (lib "SYMBOLS") (part "Transistor PNP 500mA 300V MMBTA92"))
    )
    (comp (ref "T2")
      (value "MMBTA92")
      (footprint "FOOTPRINTS:SOT23-3")
      (description "Bipolar Transistors - BJT BJT, SOT-23, 300V, 500mA, PNP")
      (fields
        (field (name "MANUFACTURER PART NUMBER") "MMBTA42")
        (field (name "MANUFACTURER") "Diotec Semiconductor")
      )
      (libsource (lib "SYMBOLS") (part "Transistor PNP 500mA 300V MMBTA92"))
    )
    (comp (ref "T3")
      (value "MMBTA92")
      (footprint "FOOTPRINTS:SOT23-3")
      (description "Bipolar Transistors - BJT BJT, SOT-23, 300V, 500mA, PNP")
      (fields
        (field (name "MANUFACTURER PART NUMBER") "MMBTA42")
        (field (name "MANUFACTURER") "Diotec Semiconductor")
      )
      (libsource (lib "SYMBOLS") (part "Transistor PNP 500mA 300V MMBTA92"))
    )
    (comp (ref "T4")
      (value "MMBTA92")
      (footprint "FOOTPRINTS:SOT23-3")
      (description "Bipolar Transistors - BJT BJT, SOT-23, 300V, 500mA, PNP")
      (fields
        (field (name "MANUFACTURER PART NUMBER") "MMBTA42")
        (field (name "MANUFACTURER") "Diotec Semiconductor")
      )
      (libsource (lib "SYMBOLS") (part "Transistor PNP 500mA 300V MMBTA92"))
    )
    (comp (ref "T5")
      (value "MMBTA92")
      (footprint "FOOTPRINTS:SOT23-3")
      (description "Bipolar Transistors - BJT BJT, SOT-23, 300V, 500mA, PNP")
      (fields
        (field (name "MANUFACTURER PART NUMBER") "MMBTA42")
        (field (name "MANUFACTURER") "Diotec Semiconductor")
      )
      (libsource (lib "SYMBOLS") (part "Transistor PNP 500mA 300V MMBTA92"))
    )
    (comp (ref "T6")
      (value "MMBTA92")
      (footprint "FOOTPRINTS:SOT23-3")
      (description "Bipolar Transistors - BJT BJT, SOT-23, 300V, 500mA, PNP")
      (fields
        (field (name "MANUFACTURER PART NUMBER") "MMBTA42")
        (field (name "MANUFACTURER") "Diotec Semiconductor")
      )
      (libsource (lib "SYMBOLS") (part "Transistor PNP 500mA 300V MMBTA92"))
    )
    (comp (ref "T7")
      (value "MMBTA42")
      (footprint "FOOTPRINTS:SOT23-3")
      (description "Bipolar Transistors - BJT BJT, SOT-23, 300V, 500mA, NPN")
      (fields (field (name "MANUFACTURER") "Diotec Semiconductor"))
      (libsource (lib "SYMBOLS") (part "Transistor NPN 500mA 300V MMBTA42"))
    )
    (comp (ref "T8")
      (value "MMBTA42")
      (footprint "FOOTPRINTS:SOT23-3")
      (description "Bipolar Transistors - BJT BJT, SOT-23, 300V, 500mA, NPN")
      (fields (field (name "MANUFACTURER") "Diotec Semiconductor"))
      (libsource (lib "SYMBOLS") (part "Transistor NPN 500mA 300V MMBTA42"))
    )
    (comp (ref "T9")
      (value "MMBTA42")
      (footprint "FOOTPRINTS:SOT23-3")
      (description "Bipolar Transistors - BJT BJT, SOT-23, 300V, 500mA, NPN")
      (fields (field (name "MANUFACTURER") "Diotec Semiconductor"))
      (libsource (lib "SYMBOLS") (part "Transistor NPN 500mA 300V MMBTA42"))
    )
    (comp (ref "T10")
      (value "MMBTA42")
      (footprint "FOOTPRINTS:SOT23-3")
      (description "Bipolar Transistors - BJT BJT, SOT-23, 300V, 500mA, NPN")
      (fields (field (name "MANUFACTURER") "Diotec Semiconductor"))
      (libsource (lib "SYMBOLS") (part "Transistor NPN 500mA 300V MMBTA42"))
    )
    (comp (ref "T11")
      (value "MMBTA42")
      (footprint "FOOTPRINTS:SOT23-3")
      (description "Bipolar Transistors - BJT BJT, SOT-23, 300V, 500mA, NPN")
      (fields (field (name "MANUFACTURER") "Diotec Semiconductor"))
      (libsource (lib "SYMBOLS") (part "Transistor NPN 500mA 300V MMBTA42"))
    )
    (comp (ref "T12")
      (value "MMBTA42")
      (footprint "FOOTPRINTS:SOT23-3")
      (description "Bipolar Transistors - BJT BJT, SOT-23, 300V, 500mA, NPN")
      (fields (field (name "MANUFACTURER") "Diotec Semiconductor"))
      (libsource (lib "SYMBOLS") (part "Transistor NPN 500mA 300V MMBTA42"))
    )
    (comp (ref "T13")
      (value "MMBTA42")
      (footprint "FOOTPRINTS:SOT23-3")
      (description "Bipolar Transistors - BJT BJT, SOT-23, 300V, 500mA, NPN")
      (fields (field (name "MANUFACTURER") "Diotec Semiconductor"))
      (libsource (lib "SYMBOLS") (part "Transistor NPN 500mA 300V MMBTA42"))
    )
    (comp (ref "T14")
      (value "MMBTA42")
      (footprint "FOOTPRINTS:SOT23-3")
      (description "Bipolar Transistors - BJT BJT, SOT-23, 300V, 500mA, NPN")
      (fields (field (name "MANUFACTURER") "Diotec Semiconductor"))
      (libsource (lib "SYMBOLS") (part "Transistor NPN 500mA 300V MMBTA42"))
    )
    (comp (ref "T15")
      (value "MMBTA42")
      (footprint "FOOTPRINTS:SOT23-3")
      (description "Bipolar Transistors - BJT BJT, SOT-23, 300V, 500mA, NPN")
      (fields (field (name "MANUFACTURER") "Diotec Semiconductor"))
      (libsource (lib "SYMBOLS") (part "Transistor NPN 500mA 300V MMBTA42"))
    )
    (comp (ref "T16")
      (value "MMBTA42")
      (footprint "FOOTPRINTS:SOT23-3")
      (description "Bipolar Transistors - BJT BJT, SOT-23, 300V, 500mA, NPN")
      (fields (field (name "MANUFACTURER") "Diotec Semiconductor"))
      (libsource (lib "SYMBOLS") (part "Transistor NPN 500mA 300V MMBTA42"))
    )
    (comp (ref "T17")
      (value "MMBTA42")
      (footprint "FOOTPRINTS:SOT23-3")
      (description "Bipolar Transistors - BJT BJT, SOT-23, 300V, 500mA, NPN")
      (fields (field (name "MANUFACTURER") "Diotec Semiconductor"))
      (libsource (lib "SYMBOLS") (part "Transistor NPN 500mA 300V MMBTA42"))
    )
    (comp (ref "T18")
      (value "MMBTA42")
      (footprint "FOOTPRINTS:SOT23-3")
      (description "Bipolar Transistors - BJT BJT, SOT-23, 300V, 500mA, NPN")
      (fields (field (name "MANUFACTURER") "Diotec Semiconductor"))
      (libsource (lib "SYMBOLS") (part "Transistor NPN 500mA 300V MMBTA42"))
    )
    (comp (ref "T19")
      (value "MMBTA42")
      (footprint "FOOTPRINTS:SOT23-3")
      (description "Bipolar Transistors - BJT BJT, SOT-23, 300V, 500mA, NPN")
      (fields (field (name "MANUFACTURER") "Diotec Semiconductor"))
      (libsource (lib "SYMBOLS") (part "Transistor NPN 500mA 300V MMBTA42"))
    )
    (comp (ref "T20")
      (value "MMBTA42")
      (footprint "FOOTPRINTS:SOT23-3")
      (description "Bipolar Transistors - BJT BJT, SOT-23, 300V, 500mA, NPN")
      (fields (field (name "MANUFACTURER") "Diotec Semiconductor"))
      (libsource (lib "SYMBOLS") (part "Transistor NPN 500mA 300V MMBTA42"))
    )
    (comp (ref "T21")
      (value "MMBTA42")
      (footprint "FOOTPRINTS:SOT23-3")
      (description "Bipolar Transistors - BJT BJT, SOT-23, 300V, 500mA, NPN")
      (fields (field (name "MANUFACTURER") "Diotec Semiconductor"))
      (libsource (lib "SYMBOLS") (part "Transistor NPN 500mA 300V MMBTA42"))
    )
    (comp (ref "T22")
      (value "MMBTA42")
      (footprint "FOOTPRINTS:SOT23-3")
      (description "Bipolar Transistors - BJT BJT, SOT-23, 300V, 500mA, NPN")
      (fields (field (name "MANUFACTURER") "Diotec Semiconductor"))
      (libsource (lib "SYMBOLS") (part "Transistor NPN 500mA 300V MMBTA42"))
    )
    (comp (ref "T23")
      (value "MMBTA42")
      (footprint "FOOTPRINTS:SOT23-3")
      (description "Bipolar Transistors - BJT BJT, SOT-23, 300V, 500mA, NPN")
      (fields (field (name "MANUFACTURER") "Diotec Semiconductor"))
      (libsource (lib "SYMBOLS") (part "Transistor NPN 500mA 300V MMBTA42"))
    )
    (comp (ref "T24")
      (value "MMBTA42")
      (footprint "FOOTPRINTS:SOT23-3")
      (description "Bipolar Transistors - BJT BJT, SOT-23, 300V, 500mA, NPN")
      (fields (field (name "MANUFACTURER") "Diotec Semiconductor"))
      (libsource (lib "SYMBOLS") (part "Transistor NPN 500mA 300V MMBTA42"))
    )
    (comp (ref "T25")
      (value "MMBTA42")
      (footprint "FOOTPRINTS:SOT23-3")
      (description "Bipolar Transistors - BJT BJT, SOT-23, 300V, 500mA, NPN")
      (fields (field (name "MANUFACTURER") "Diotec Semiconductor"))
      (libsource (lib "SYMBOLS") (part "Transistor NPN 500mA 300V MMBTA42"))
    )
    (comp (ref "T26")
      (value "MMBTA42")
      (footprint "FOOTPRINTS:SOT23-3")
      (description "Bipolar Transistors - BJT BJT, SOT-23, 300V, 500mA, NPN")
      (fields (field (name "MANUFACTURER") "Diotec Semiconductor"))
      (libsource (lib "SYMBOLS") (part "Transistor NPN 500mA 300V MMBTA42"))
    )
    (comp (ref "T27")
      (value "MMBTA42")
      (footprint "FOOTPRINTS:SOT23-3")
      (description "Bipolar Transistors - BJT BJT, SOT-23, 300V, 500mA, NPN")
      (fields (field (name "MANUFACTURER") "Diotec Semiconductor"))
      (libsource (lib "SYMBOLS") (part "Transistor NPN 500mA 300V MMBTA42"))
    )
    (comp (ref "T28")
      (value "MMBTA42")
      (footprint "FOOTPRINTS:SOT23-3")
      (description "Bipolar Transistors - BJT BJT, SOT-23, 300V, 500mA, NPN")
      (fields (field (name "MANUFACTURER") "Diotec Semiconductor"))
      (libsource (lib "SYMBOLS") (part "Transistor NPN 500mA 300V MMBTA42"))
    )
    (comp (ref "T29")
      (value "MMBTA42")
      (footprint "FOOTPRINTS:SOT23-3")
      (description "Bipolar Transistors - BJT BJT, SOT-23, 300V, 500mA, NPN")
      (fields (field (name "MANUFACTURER") "Diotec Semiconductor"))
      (libsource (lib "SYMBOLS") (part "Transistor NPN 500mA 300V MMBTA42"))
    )
    (comp (ref "T30")
      (value "MMBTA42")
      (footprint "FOOTPRINTS:SOT23-3")
      (description "Bipolar Transistors - BJT BJT, SOT-23, 300V, 500mA, NPN")
      (fields (field (name "MANUFACTURER") "Diotec Semiconductor"))
      (libsource (lib "SYMBOLS") (part "Transistor NPN 500mA 300V MMBTA42"))
    )
    (comp (ref "TP1")
      (value "1mm")
      (footprint "FOOTPRINTS:TEST POINT 1MM")
      (description "Tesp Point 1mm")
      (libsource (lib "SYMBOLS") (part "Mechanical Test Point 1mm"))
    )
    (comp (ref "TP2")
      (value "1mm")
      (footprint "FOOTPRINTS:TEST POINT 1MM")
      (description "Tesp Point 1mm")
      (libsource (lib "SYMBOLS") (part "Mechanical Test Point 1mm"))
    )
    (comp (ref "TP3")
      (value "1mm")
      (footprint "FOOTPRINTS:TEST POINT 1MM")
      (description "Tesp Point 1mm")
      (libsource (lib "SYMBOLS") (part "Mechanical Test Point 1mm"))
    )
    (comp (ref "TP4")
      (value "1mm")
      (footprint "FOOTPRINTS:TEST POINT 1MM")
      (description "Tesp Point 1mm")
      (libsource (lib "SYMBOLS") (part "Mechanical Test Point 1mm"))
    )
    (comp (ref "TP5")
      (value "1mm")
      (footprint "FOOTPRINTS:TEST POINT 1MM")
      (description "Tesp Point 1mm")
      (libsource (lib "SYMBOLS") (part "Mechanical Test Point 1mm"))
    )
    (comp (ref "TP6")
      (value "1mm")
      (footprint "FOOTPRINTS:TEST POINT 1MM")
      (description "Tesp Point 1mm")
      (libsource (lib "SYMBOLS") (part "Mechanical Test Point 1mm"))
    )
    (comp (ref "TP7")
      (value "1mm")
      (footprint "FOOTPRINTS:TEST POINT 1MM")
      (description "Tesp Point 1mm")
      (libsource (lib "SYMBOLS") (part "Mechanical Test Point 1mm"))
    )
    (comp (ref "TP8")
      (value "1mm")
      (footprint "FOOTPRINTS:TEST POINT 1MM")
      (description "Tesp Point 1mm")
      (libsource (lib "SYMBOLS") (part "Mechanical Test Point 1mm"))
    )
    (comp (ref "TP9")
      (value "1mm")
      (footprint "FOOTPRINTS:TEST POINT 1MM")
      (description "Tesp Point 1mm")
      (libsource (lib "SYMBOLS") (part "Mechanical Test Point 1mm"))
    )
    (comp (ref "TP10")
      (value "1mm")
      (footprint "FOOTPRINTS:TEST POINT 1MM")
      (description "Tesp Point 1mm")
      (libsource (lib "SYMBOLS") (part "Mechanical Test Point 1mm"))
    )
    (comp (ref "TP11")
      (value "1mm")
      (footprint "FOOTPRINTS:TEST POINT 1MM")
      (description "Tesp Point 1mm")
      (libsource (lib "SYMBOLS") (part "Mechanical Test Point 1mm"))
    )
    (comp (ref "TP12")
      (value "1mm")
      (footprint "FOOTPRINTS:TEST POINT 1MM")
      (description "Tesp Point 1mm")
      (libsource (lib "SYMBOLS") (part "Mechanical Test Point 1mm"))
    )
    (comp (ref "TP13")
      (value "1mm")
      (footprint "FOOTPRINTS:TEST POINT 1MM")
      (description "Tesp Point 1mm")
      (libsource (lib "SYMBOLS") (part "Mechanical Test Point 1mm"))
    )
    (comp (ref "TP14")
      (value "1mm")
      (footprint "FOOTPRINTS:TEST POINT 1MM")
      (description "Tesp Point 1mm")
      (libsource (lib "SYMBOLS") (part "Mechanical Test Point 1mm"))
    )
    (comp (ref "TP15")
      (value "1mm")
      (footprint "FOOTPRINTS:TEST POINT 1MM")
      (description "Tesp Point 1mm")
      (libsource (lib "SYMBOLS") (part "Mechanical Test Point 1mm"))
    )
    (comp (ref "TP16")
      (value "1mm")
      (footprint "FOOTPRINTS:TEST POINT 1MM")
      (description "Tesp Point 1mm")
      (libsource (lib "SYMBOLS") (part "Mechanical Test Point 1mm"))
    )
    (comp (ref "TP17")
      (value "1mm")
      (footprint "FOOTPRINTS:TEST POINT 1MM")
      (description "Tesp Point 1mm")
      (libsource (lib "SYMBOLS") (part "Mechanical Test Point 1mm"))
    )
    (comp (ref "TP18")
      (value "1mm")
      (footprint "FOOTPRINTS:TEST POINT 1MM")
      (description "Tesp Point 1mm")
      (libsource (lib "SYMBOLS") (part "Mechanical Test Point 1mm"))
    )
    (comp (ref "TP19")
      (value "1mm")
      (footprint "FOOTPRINTS:TEST POINT 1MM")
      (description "Tesp Point 1mm")
      (libsource (lib "SYMBOLS") (part "Mechanical Test Point 1mm"))
    )
    (comp (ref "TP20")
      (value "1mm")
      (footprint "FOOTPRINTS:TEST POINT 1MM")
      (description "Tesp Point 1mm")
      (libsource (lib "SYMBOLS") (part "Mechanical Test Point 1mm"))
    )
    (comp (ref "TP21")
      (value "1mm")
      (footprint "FOOTPRINTS:TEST POINT 1MM")
      (description "Tesp Point 1mm")
      (libsource (lib "SYMBOLS") (part "Mechanical Test Point 1mm"))
    )
    (comp (ref "TP22")
      (value "1mm")
      (footprint "FOOTPRINTS:TEST POINT 1MM")
      (description "Tesp Point 1mm")
      (libsource (lib "SYMBOLS") (part "Mechanical Test Point 1mm"))
    )
    (comp (ref "TP23")
      (value "1mm")
      (footprint "FOOTPRINTS:TEST POINT 1MM")
      (description "Tesp Point 1mm")
      (libsource (lib "SYMBOLS") (part "Mechanical Test Point 1mm"))
    )
    (comp (ref "TP24")
      (value "1mm")
      (footprint "FOOTPRINTS:TEST POINT 1MM")
      (description "Tesp Point 1mm")
      (libsource (lib "SYMBOLS") (part "Mechanical Test Point 1mm"))
    )
    (comp (ref "V1")
      (value "IN-14")
      (footprint "FOOTPRINTS:IN-14")
      (description "Nixie IN-14")
      (libsource (lib "SYMBOLS") (part "Tube Nixie IN-14"))
    )
    (comp (ref "V2")
      (value "IN-14")
      (footprint "FOOTPRINTS:IN-14")
      (description "Nixie IN-14")
      (libsource (lib "SYMBOLS") (part "Tube Nixie IN-14"))
    )
    (comp (ref "V3")
      (value "IN-14")
      (footprint "FOOTPRINTS:IN-14")
      (description "Nixie IN-14")
      (libsource (lib "SYMBOLS") (part "Tube Nixie IN-14"))
    )
    (comp (ref "V4")
      (value "IN-14")
      (footprint "FOOTPRINTS:IN-14")
      (description "Nixie IN-14")
      (libsource (lib "SYMBOLS") (part "Tube Nixie IN-14"))
    )
    (comp (ref "V5")
      (value "IN-14")
      (footprint "FOOTPRINTS:IN-14")
      (description "Nixie IN-14")
      (libsource (lib "SYMBOLS") (part "Tube Nixie IN-14"))
    )
    (comp (ref "V6")
      (value "IN-14")
      (footprint "FOOTPRINTS:IN-14")
      (description "Nixie IN-14")
      (libsource (lib "SYMBOLS") (part "Tube Nixie IN-14"))
    )
    (comp (ref "V7")
      (value "IN-3")
      (footprint "FOOTPRINTS:IN-3")
      (description "Nixie IN-8-2")
      (libsource (lib "SYMBOLS") (part "Tube Neon IN-3"))
    )
    (comp (ref "V8")
      (value "IN-3")
      (footprint "FOOTPRINTS:IN-3")
      (description "Nixie IN-8-2")
      (libsource (lib "SYMBOLS") (part "Tube Neon IN-3"))
    )
  )
  (nets
    (net (code "1") (name "+12V") (class "Default")
      (node (ref "D1") (pin "1") (pinfunction "1_1") (pintype "passive"))
      (node (ref "D2") (pin "1") (pinfunction "1_1") (pintype "passive"))
      (node (ref "D3") (pin "1") (pinfunction "1_1") (pintype "passive"))
      (node (ref "D4") (pin "1") (pinfunction "1_1") (pintype "passive"))
      (node (ref "D5") (pin "1") (pinfunction "1_1") (pintype "passive"))
      (node (ref "D6") (pin "1") (pinfunction "1_1") (pintype "passive"))
      (node (ref "J4") (pin "6") (pinfunction "6_6") (pintype "passive"))
    )
    (net (code "2") (name "+HV") (class "Default")
      (node (ref "J4") (pin "1") (pinfunction "1_1") (pintype "passive"))
      (node (ref "R1") (pin "2") (pinfunction "2_2") (pintype "passive"))
      (node (ref "R2") (pin "2") (pinfunction "2_2") (pintype "passive"))
      (node (ref "R3") (pin "2") (pinfunction "2_2") (pintype "passive"))
      (node (ref "R4") (pin "2") (pinfunction "2_2") (pintype "passive"))
      (node (ref "R5") (pin "2") (pinfunction "2_2") (pintype "passive"))
      (node (ref "R6") (pin "2") (pinfunction "2_2") (pintype "passive"))
      (node (ref "T1") (pin "2") (pinfunction "E_2") (pintype "passive"))
      (node (ref "T2") (pin "2") (pinfunction "E_2") (pintype "passive"))
      (node (ref "T3") (pin "2") (pinfunction "E_2") (pintype "passive"))
      (node (ref "T4") (pin "2") (pinfunction "E_2") (pintype "passive"))
      (node (ref "T5") (pin "2") (pinfunction "E_2") (pintype "passive"))
      (node (ref "T6") (pin "2") (pinfunction "E_2") (pintype "passive"))
      (node (ref "V7") (pin "2") (pinfunction "2_2") (pintype "passive"))
      (node (ref "V8") (pin "2") (pinfunction "2_2") (pintype "passive"))
    )
    (net (code "4") (name "/A1") (class "Default")
      (node (ref "R19") (pin "1") (pinfunction "1_1") (pintype "passive"))
      (node (ref "TP1") (pin "1") (pinfunction "1_1") (pintype "passive"))
      (node (ref "V1") (pin "1") (pinfunction "A_1") (pintype "passive"))
    )
    (net (code "5") (name "/A2") (class "Default")
      (node (ref "R20") (pin "1") (pinfunction "1_1") (pintype "passive"))
      (node (ref "TP2") (pin "1") (pinfunction "1_1") (pintype "passive"))
      (node (ref "V2") (pin "1") (pinfunction "A_1") (pintype "passive"))
    )
    (net (code "6") (name "/A3") (class "Default")
      (node (ref "R21") (pin "1") (pinfunction "1_1") (pintype "passive"))
      (node (ref "TP3") (pin "1") (pinfunction "1_1") (pintype "passive"))
      (node (ref "V3") (pin "1") (pinfunction "A_1") (pintype "passive"))
    )
    (net (code "7") (name "/A4") (class "Default")
      (node (ref "R22") (pin "1") (pinfunction "1_1") (pintype "passive"))
      (node (ref "TP4") (pin "1") (pinfunction "1_1") (pintype "passive"))
      (node (ref "V4") (pin "1") (pinfunction "A_1") (pintype "passive"))
    )
    (net (code "8") (name "/A5") (class "Default")
      (node (ref "R23") (pin "1") (pinfunction "1_1") (pintype "passive"))
      (node (ref "TP5") (pin "1") (pinfunction "1_1") (pintype "passive"))
      (node (ref "V5") (pin "1") (pinfunction "A_1") (pintype "passive"))
    )
    (net (code "9") (name "/A6") (class "Default")
      (node (ref "R24") (pin "1") (pinfunction "1_1") (pintype "passive"))
      (node (ref "TP6") (pin "1") (pinfunction "1_1") (pintype "passive"))
      (node (ref "V6") (pin "1") (pinfunction "A_1") (pintype "passive"))
    )
    (net (code "10") (name "/ANODE1") (class "Default")
      (node (ref "J3") (pin "1") (pinfunction "1_1") (pintype "passive"))
      (node (ref "R13") (pin "1") (pinfunction "1_1") (pintype "passive"))
    )
    (net (code "11") (name "/ANODE2") (class "Default")
      (node (ref "J3") (pin "2") (pinfunction "2_2") (pintype "passive"))
      (node (ref "R14") (pin "1") (pinfunction "1_1") (pintype "passive"))
    )
    (net (code "12") (name "/ANODE3") (class "Default")
      (node (ref "J3") (pin "3") (pinfunction "3_3") (pintype "passive"))
      (node (ref "R15") (pin "1") (pinfunction "1_1") (pintype "passive"))
    )
    (net (code "13") (name "/ANODE4") (class "Default")
      (node (ref "J3") (pin "4") (pinfunction "4_4") (pintype "passive"))
      (node (ref "R16") (pin "1") (pinfunction "1_1") (pintype "passive"))
    )
    (net (code "14") (name "/ANODE5") (class "Default")
      (node (ref "J3") (pin "5") (pinfunction "5_5") (pintype "passive"))
      (node (ref "R17") (pin "1") (pinfunction "1_1") (pintype "passive"))
    )
    (net (code "15") (name "/ANODE6") (class "Default")
      (node (ref "J3") (pin "6") (pinfunction "6_6") (pintype "passive"))
      (node (ref "R18") (pin "1") (pinfunction "1_1") (pintype "passive"))
    )
    (net (code "16") (name "/B1") (class "Default")
      (node (ref "R57") (pin "2") (pinfunction "2_2") (pintype "passive"))
      (node (ref "TP17") (pin "1") (pinfunction "1_1") (pintype "passive"))
      (node (ref "V7") (pin "1") (pinfunction "1_1") (pintype "passive"))
    )
    (net (code "17") (name "/B2") (class "Default")
      (node (ref "R58") (pin "2") (pinfunction "2_2") (pintype "passive"))
      (node (ref "TP18") (pin "1") (pinfunction "1_1") (pintype "passive"))
      (node (ref "V8") (pin "1") (pinfunction "1_1") (pintype "passive"))
    )
    (net (code "18") (name "/BULB1") (class "Default")
      (node (ref "J1") (pin "6") (pinfunction "6_6") (pintype "passive"))
      (node (ref "R65") (pin "1") (pinfunction "1_1") (pintype "passive"))
    )
    (net (code "19") (name "/BULB2") (class "Default")
      (node (ref "J2") (pin "6") (pinfunction "6_6") (pintype "passive"))
      (node (ref "R66") (pin "1") (pinfunction "1_1") (pintype "passive"))
    )
    (net (code "20") (name "/CATHODE0") (class "Default")
      (node (ref "J1") (pin "1") (pinfunction "1_1") (pintype "passive"))
      (node (ref "R40") (pin "1") (pinfunction "1_1") (pintype "passive"))
    )
    (net (code "21") (name "/CATHODE1") (class "Default")
      (node (ref "J1") (pin "2") (pinfunction "2_2") (pintype "passive"))
      (node (ref "R31") (pin "1") (pinfunction "1_1") (pintype "passive"))
    )
    (net (code "22") (name "/CATHODE2") (class "Default")
      (node (ref "J1") (pin "3") (pinfunction "3_3") (pintype "passive"))
      (node (ref "R32") (pin "1") (pinfunction "1_1") (pintype "passive"))
    )
    (net (code "23") (name "/CATHODE3") (class "Default")
      (node (ref "J1") (pin "4") (pinfunction "4_4") (pintype "passive"))
      (node (ref "R33") (pin "1") (pinfunction "1_1") (pintype "passive"))
    )
    (net (code "24") (name "/CATHODE4") (class "Default")
      (node (ref "J1") (pin "5") (pinfunction "5_5") (pintype "passive"))
      (node (ref "R34") (pin "1") (pinfunction "1_1") (pintype "passive"))
    )
    (net (code "25") (name "/CATHODE5") (class "Default")
      (node (ref "J2") (pin "1") (pinfunction "1_1") (pintype "passive"))
      (node (ref "R35") (pin "1") (pinfunction "1_1") (pintype "passive"))
    )
    (net (code "26") (name "/CATHODE6") (class "Default")
      (node (ref "J2") (pin "2") (pinfunction "2_2") (pintype "passive"))
      (node (ref "R36") (pin "1") (pinfunction "1_1") (pintype "passive"))
    )
    (net (code "27") (name "/CATHODE7") (class "Default")
      (node (ref "J2") (pin "3") (pinfunction "3_3") (pintype "passive"))
      (node (ref "R37") (pin "1") (pinfunction "1_1") (pintype "passive"))
    )
    (net (code "28") (name "/CATHODE8") (class "Default")
      (node (ref "J2") (pin "4") (pinfunction "4_4") (pintype "passive"))
      (node (ref "R38") (pin "1") (pinfunction "1_1") (pintype "passive"))
    )
    (net (code "29") (name "/CATHODE9") (class "Default")
      (node (ref "J2") (pin "5") (pinfunction "5_5") (pintype "passive"))
      (node (ref "R39") (pin "1") (pinfunction "1_1") (pintype "passive"))
    )
    (net (code "30") (name "/K0") (class "Default")
      (node (ref "T22") (pin "3") (pinfunction "C_3") (pintype "passive"))
      (node (ref "TP16") (pin "1") (pinfunction "1_1") (pintype "passive"))
      (node (ref "V1") (pin "12") (pinfunction "0_12") (pintype "passive"))
      (node (ref "V2") (pin "12") (pinfunction "0_12") (pintype "passive"))
      (node (ref "V3") (pin "12") (pinfunction "0_12") (pintype "passive"))
      (node (ref "V4") (pin "12") (pinfunction "0_12") (pintype "passive"))
      (node (ref "V5") (pin "12") (pinfunction "0_12") (pintype "passive"))
      (node (ref "V6") (pin "12") (pinfunction "0_12") (pintype "passive"))
    )
    (net (code "31") (name "/K1") (class "Default")
      (node (ref "T13") (pin "3") (pinfunction "C_3") (pintype "passive"))
      (node (ref "TP7") (pin "1") (pinfunction "1_1") (pintype "passive"))
      (node (ref "V1") (pin "3") (pinfunction "1_3") (pintype "passive"))
      (node (ref "V2") (pin "3") (pinfunction "1_3") (pintype "passive"))
      (node (ref "V3") (pin "3") (pinfunction "1_3") (pintype "passive"))
      (node (ref "V4") (pin "3") (pinfunction "1_3") (pintype "passive"))
      (node (ref "V5") (pin "3") (pinfunction "1_3") (pintype "passive"))
      (node (ref "V6") (pin "3") (pinfunction "1_3") (pintype "passive"))
    )
    (net (code "32") (name "/K2") (class "Default")
      (node (ref "T14") (pin "3") (pinfunction "C_3") (pintype "passive"))
      (node (ref "TP8") (pin "1") (pinfunction "1_1") (pintype "passive"))
      (node (ref "V1") (pin "4") (pinfunction "2_4") (pintype "passive"))
      (node (ref "V2") (pin "4") (pinfunction "2_4") (pintype "passive"))
      (node (ref "V3") (pin "4") (pinfunction "2_4") (pintype "passive"))
      (node (ref "V4") (pin "4") (pinfunction "2_4") (pintype "passive"))
      (node (ref "V5") (pin "4") (pinfunction "2_4") (pintype "passive"))
      (node (ref "V6") (pin "4") (pinfunction "2_4") (pintype "passive"))
    )
    (net (code "33") (name "/K3") (class "Default")
      (node (ref "T15") (pin "3") (pinfunction "C_3") (pintype "passive"))
      (node (ref "TP9") (pin "1") (pinfunction "1_1") (pintype "passive"))
      (node (ref "V1") (pin "5") (pinfunction "3_5") (pintype "passive"))
      (node (ref "V2") (pin "5") (pinfunction "3_5") (pintype "passive"))
      (node (ref "V3") (pin "5") (pinfunction "3_5") (pintype "passive"))
      (node (ref "V4") (pin "5") (pinfunction "3_5") (pintype "passive"))
      (node (ref "V5") (pin "5") (pinfunction "3_5") (pintype "passive"))
      (node (ref "V6") (pin "5") (pinfunction "3_5") (pintype "passive"))
    )
    (net (code "34") (name "/K4") (class "Default")
      (node (ref "T16") (pin "3") (pinfunction "C_3") (pintype "passive"))
      (node (ref "TP10") (pin "1") (pinfunction "1_1") (pintype "passive"))
      (node (ref "V1") (pin "6") (pinfunction "4_6") (pintype "passive"))
      (node (ref "V2") (pin "6") (pinfunction "4_6") (pintype "passive"))
      (node (ref "V3") (pin "6") (pinfunction "4_6") (pintype "passive"))
      (node (ref "V4") (pin "6") (pinfunction "4_6") (pintype "passive"))
      (node (ref "V5") (pin "6") (pinfunction "4_6") (pintype "passive"))
      (node (ref "V6") (pin "6") (pinfunction "4_6") (pintype "passive"))
    )
    (net (code "35") (name "/K5") (class "Default")
      (node (ref "T17") (pin "3") (pinfunction "C_3") (pintype "passive"))
      (node (ref "TP11") (pin "1") (pinfunction "1_1") (pintype "passive"))
      (node (ref "V1") (pin "7") (pinfunction "5_7") (pintype "passive"))
      (node (ref "V2") (pin "7") (pinfunction "5_7") (pintype "passive"))
      (node (ref "V3") (pin "7") (pinfunction "5_7") (pintype "passive"))
      (node (ref "V4") (pin "7") (pinfunction "5_7") (pintype "passive"))
      (node (ref "V5") (pin "7") (pinfunction "5_7") (pintype "passive"))
      (node (ref "V6") (pin "7") (pinfunction "5_7") (pintype "passive"))
    )
    (net (code "36") (name "/K6") (class "Default")
      (node (ref "T18") (pin "3") (pinfunction "C_3") (pintype "passive"))
      (node (ref "TP12") (pin "1") (pinfunction "1_1") (pintype "passive"))
      (node (ref "V1") (pin "8") (pinfunction "6_8") (pintype "passive"))
      (node (ref "V2") (pin "8") (pinfunction "6_8") (pintype "passive"))
      (node (ref "V3") (pin "8") (pinfunction "6_8") (pintype "passive"))
      (node (ref "V4") (pin "8") (pinfunction "6_8") (pintype "passive"))
      (node (ref "V5") (pin "8") (pinfunction "6_8") (pintype "passive"))
      (node (ref "V6") (pin "8") (pinfunction "6_8") (pintype "passive"))
    )
    (net (code "37") (name "/K7") (class "Default")
      (node (ref "T19") (pin "3") (pinfunction "C_3") (pintype "passive"))
      (node (ref "TP13") (pin "1") (pinfunction "1_1") (pintype "passive"))
      (node (ref "V1") (pin "9") (pinfunction "7_9") (pintype "passive"))
      (node (ref "V2") (pin "9") (pinfunction "7_9") (pintype "passive"))
      (node (ref "V3") (pin "9") (pinfunction "7_9") (pintype "passive"))
      (node (ref "V4") (pin "9") (pinfunction "7_9") (pintype "passive"))
      (node (ref "V5") (pin "9") (pinfunction "7_9") (pintype "passive"))
      (node (ref "V6") (pin "9") (pinfunction "7_9") (pintype "passive"))
    )
    (net (code "38") (name "/K8") (class "Default")
      (node (ref "T20") (pin "3") (pinfunction "C_3") (pintype "passive"))
      (node (ref "TP14") (pin "1") (pinfunction "1_1") (pintype "passive"))
      (node (ref "V1") (pin "10") (pinfunction "8_10") (pintype "passive"))
      (node (ref "V2") (pin "10") (pinfunction "8_10") (pintype "passive"))
      (node (ref "V3") (pin "10") (pinfunction "8_10") (pintype "passive"))
      (node (ref "V4") (pin "10") (pinfunction "8_10") (pintype "passive"))
      (node (ref "V5") (pin "10") (pinfunction "8_10") (pintype "passive"))
      (node (ref "V6") (pin "10") (pinfunction "8_10") (pintype "passive"))
    )
    (net (code "39") (name "/K9") (class "Default")
      (node (ref "T21") (pin "3") (pinfunction "C_3") (pintype "passive"))
      (node (ref "TP15") (pin "1") (pinfunction "1_1") (pintype "passive"))
      (node (ref "V1") (pin "11") (pinfunction "9_11") (pintype "passive"))
      (node (ref "V2") (pin "11") (pinfunction "9_11") (pintype "passive"))
      (node (ref "V3") (pin "11") (pinfunction "9_11") (pintype "passive"))
      (node (ref "V4") (pin "11") (pinfunction "9_11") (pintype "passive"))
      (node (ref "V5") (pin "11") (pinfunction "9_11") (pintype "passive"))
      (node (ref "V6") (pin "11") (pinfunction "9_11") (pintype "passive"))
    )
    (net (code "40") (name "/LED1") (class "Default")
      (node (ref "R51") (pin "1") (pinfunction "1_1") (pintype "passive"))
      (node (ref "T23") (pin "3") (pinfunction "C_3") (pintype "passive"))
      (node (ref "TP19") (pin "1") (pinfunction "1_1") (pintype "passive"))
    )
    (net (code "41") (name "/LED2") (class "Default")
      (node (ref "R52") (pin "1") (pinfunction "1_1") (pintype "passive"))
      (node (ref "T24") (pin "3") (pinfunction "C_3") (pintype "passive"))
      (node (ref "TP20") (pin "1") (pinfunction "1_1") (pintype "passive"))
    )
    (net (code "42") (name "/LED3") (class "Default")
      (node (ref "R53") (pin "1") (pinfunction "1_1") (pintype "passive"))
      (node (ref "T25") (pin "3") (pinfunction "C_3") (pintype "passive"))
      (node (ref "TP21") (pin "1") (pinfunction "1_1") (pintype "passive"))
    )
    (net (code "43") (name "/LED4") (class "Default")
      (node (ref "R54") (pin "1") (pinfunction "1_1") (pintype "passive"))
      (node (ref "T26") (pin "3") (pinfunction "C_3") (pintype "passive"))
      (node (ref "TP22") (pin "1") (pinfunction "1_1") (pintype "passive"))
    )
    (net (code "44") (name "/LED5") (class "Default")
      (node (ref "R55") (pin "1") (pinfunction "1_1") (pintype "passive"))
      (node (ref "T27") (pin "3") (pinfunction "C_3") (pintype "passive"))
      (node (ref "TP23") (pin "1") (pinfunction "1_1") (pintype "passive"))
    )
    (net (code "45") (name "/LED6") (class "Default")
      (node (ref "R56") (pin "1") (pinfunction "1_1") (pintype "passive"))
      (node (ref "T28") (pin "3") (pinfunction "C_3") (pintype "passive"))
      (node (ref "TP24") (pin "1") (pinfunction "1_1") (pintype "passive"))
    )
    (net (code "46") (name "/PWM") (class "Default")
      (node (ref "J4") (pin "5") (pinfunction "5_5") (pintype "passive"))
      (node (ref "R59") (pin "1") (pinfunction "1_1") (pintype "passive"))
      (node (ref "R60") (pin "1") (pinfunction "1_1") (pintype "passive"))
      (node (ref "R61") (pin "1") (pinfunction "1_1") (pintype "passive"))
      (node (ref "R62") (pin "1") (pinfunction "1_1") (pintype "passive"))
      (node (ref "R63") (pin "1") (pinfunction "1_1") (pintype "passive"))
      (node (ref "R64") (pin "1") (pinfunction "1_1") (pintype "passive"))
    )
    (net (code "47") (name "GND") (class "Default")
      (node (ref "J4") (pin "3") (pinfunction "3_3") (pintype "passive"))
      (node (ref "J4") (pin "4") (pinfunction "4_4") (pintype "passive"))
      (node (ref "R25") (pin "1") (pinfunction "1_1") (pintype "passive"))
      (node (ref "R26") (pin "1") (pinfunction "1_1") (pintype "passive"))
      (node (ref "R27") (pin "1") (pinfunction "1_1") (pintype "passive"))
      (node (ref "R28") (pin "1") (pinfunction "1_1") (pintype "passive"))
      (node (ref "R29") (pin "1") (pinfunction "1_1") (pintype "passive"))
      (node (ref "R30") (pin "1") (pinfunction "1_1") (pintype "passive"))
      (node (ref "R41") (pin "1") (pinfunction "1_1") (pintype "passive"))
      (node (ref "R42") (pin "1") (pinfunction "1_1") (pintype "passive"))
      (node (ref "R43") (pin "1") (pinfunction "1_1") (pintype "passive"))
      (node (ref "R44") (pin "1") (pinfunction "1_1") (pintype "passive"))
      (node (ref "R45") (pin "1") (pinfunction "1_1") (pintype "passive"))
      (node (ref "R46") (pin "1") (pinfunction "1_1") (pintype "passive"))
      (node (ref "R47") (pin "1") (pinfunction "1_1") (pintype "passive"))
      (node (ref "R48") (pin "1") (pinfunction "1_1") (pintype "passive"))
      (node (ref "R49") (pin "1") (pinfunction "1_1") (pintype "passive"))
      (node (ref "R50") (pin "1") (pinfunction "1_1") (pintype "passive"))
      (node (ref "R67") (pin "1") (pinfunction "1_1") (pintype "passive"))
      (node (ref "R68") (pin "1") (pinfunction "1_1") (pintype "passive"))
      (node (ref "R69") (pin "1") (pinfunction "1_1") (pintype "passive"))
      (node (ref "R70") (pin "1") (pinfunction "1_1") (pintype "passive"))
      (node (ref "R71") (pin "1") (pinfunction "1_1") (pintype "passive"))
      (node (ref "R72") (pin "1") (pinfunction "1_1") (pintype "passive"))
      (node (ref "R73") (pin "1") (pinfunction "1_1") (pintype "passive"))
      (node (ref "R74") (pin "1") (pinfunction "1_1") (pintype "passive"))
      (node (ref "R75") (pin "1") (pinfunction "1_1") (pintype "passive"))
      (node (ref "R76") (pin "1") (pinfunction "1_1") (pintype "passive"))
      (node (ref "R77") (pin "1") (pinfunction "1_1") (pintype "passive"))
      (node (ref "R78") (pin "1") (pinfunction "1_1") (pintype "passive"))
      (node (ref "T10") (pin "2") (pinfunction "E_2") (pintype "passive"))
      (node (ref "T11") (pin "2") (pinfunction "E_2") (pintype "passive"))
      (node (ref "T12") (pin "2") (pinfunction "E_2") (pintype "passive"))
      (node (ref "T13") (pin "2") (pinfunction "E_2") (pintype "passive"))
      (node (ref "T14") (pin "2") (pinfunction "E_2") (pintype "passive"))
      (node (ref "T15") (pin "2") (pinfunction "E_2") (pintype "passive"))
      (node (ref "T16") (pin "2") (pinfunction "E_2") (pintype "passive"))
      (node (ref "T17") (pin "2") (pinfunction "E_2") (pintype "passive"))
      (node (ref "T18") (pin "2") (pinfunction "E_2") (pintype "passive"))
      (node (ref "T19") (pin "2") (pinfunction "E_2") (pintype "passive"))
      (node (ref "T20") (pin "2") (pinfunction "E_2") (pintype "passive"))
      (node (ref "T21") (pin "2") (pinfunction "E_2") (pintype "passive"))
      (node (ref "T22") (pin "2") (pinfunction "E_2") (pintype "passive"))
      (node (ref "T23") (pin "2") (pinfunction "E_2") (pintype "passive"))
      (node (ref "T24") (pin "2") (pinfunction "E_2") (pintype "passive"))
      (node (ref "T25") (pin "2") (pinfunction "E_2") (pintype "passive"))
      (node (ref "T26") (pin "2") (pinfunction "E_2") (pintype "passive"))
      (node (ref "T27") (pin "2") (pinfunction "E_2") (pintype "passive"))
      (node (ref "T28") (pin "2") (pinfunction "E_2") (pintype "passive"))
      (node (ref "T29") (pin "2") (pinfunction "E_2") (pintype "passive"))
      (node (ref "T30") (pin "2") (pinfunction "E_2") (pintype "passive"))
      (node (ref "T7") (pin "2") (pinfunction "E_2") (pintype "passive"))
      (node (ref "T8") (pin "2") (pinfunction "E_2") (pintype "passive"))
      (node (ref "T9") (pin "2") (pinfunction "E_2") (pintype "passive"))
    )
    (net (code "48") (name "Net-(A1-Pad1)") (class "Default")
      (node (ref "A1") (pin "1") (pinfunction "1_1") (pintype "passive"))
      (node (ref "R75") (pin "2") (pinfunction "2_2") (pintype "passive"))
    )
    (net (code "49") (name "Net-(A2-Pad1)") (class "Default")
      (node (ref "A2") (pin "1") (pinfunction "1_1") (pintype "passive"))
      (node (ref "R76") (pin "2") (pinfunction "2_2") (pintype "passive"))
    )
    (net (code "50") (name "Net-(A3-Pad1)") (class "Default")
      (node (ref "A3") (pin "1") (pinfunction "1_1") (pintype "passive"))
      (node (ref "R77") (pin "2") (pinfunction "2_2") (pintype "passive"))
    )
    (net (code "51") (name "Net-(A4-Pad1)") (class "Default")
      (node (ref "A4") (pin "1") (pinfunction "1_1") (pintype "passive"))
      (node (ref "R78") (pin "2") (pinfunction "2_2") (pintype "passive"))
    )
    (net (code "52") (name "Net-(D1-Pad2)") (class "Default")
      (node (ref "D1") (pin "2") (pinfunction "2_2") (pintype "passive"))
      (node (ref "R51") (pin "2") (pinfunction "2_2") (pintype "passive"))
    )
    (net (code "53") (name "Net-(D2-Pad2)") (class "Default")
      (node (ref "D2") (pin "2") (pinfunction "2_2") (pintype "passive"))
      (node (ref "R52") (pin "2") (pinfunction "2_2") (pintype "passive"))
    )
    (net (code "54") (name "Net-(D3-Pad2)") (class "Default")
      (node (ref "D3") (pin "2") (pinfunction "2_2") (pintype "passive"))
      (node (ref "R53") (pin "2") (pinfunction "2_2") (pintype "passive"))
    )
    (net (code "55") (name "Net-(D4-Pad2)") (class "Default")
      (node (ref "D4") (pin "2") (pinfunction "2_2") (pintype "passive"))
      (node (ref "R54") (pin "2") (pinfunction "2_2") (pintype "passive"))
    )
    (net (code "56") (name "Net-(D5-Pad2)") (class "Default")
      (node (ref "D5") (pin "2") (pinfunction "2_2") (pintype "passive"))
      (node (ref "R55") (pin "2") (pinfunction "2_2") (pintype "passive"))
    )
    (net (code "57") (name "Net-(D6-Pad2)") (class "Default")
      (node (ref "D6") (pin "2") (pinfunction "2_2") (pintype "passive"))
      (node (ref "R56") (pin "2") (pinfunction "2_2") (pintype "passive"))
    )
    (net (code "58") (name "Net-(T1-B)") (class "Default")
      (node (ref "R1") (pin "1") (pinfunction "1_1") (pintype "passive"))
      (node (ref "R7") (pin "2") (pinfunction "2_2") (pintype "passive"))
      (node (ref "T1") (pin "1") (pinfunction "B_1") (pintype "passive"))
    )
    (net (code "59") (name "Net-(T1-C)") (class "Default")
      (node (ref "R19") (pin "2") (pinfunction "2_2") (pintype "passive"))
      (node (ref "T1") (pin "3") (pinfunction "C_3") (pintype "passive"))
    )
    (net (code "60") (name "Net-(T2-B)") (class "Default")
      (node (ref "R2") (pin "1") (pinfunction "1_1") (pintype "passive"))
      (node (ref "R8") (pin "2") (pinfunction "2_2") (pintype "passive"))
      (node (ref "T2") (pin "1") (pinfunction "B_1") (pintype "passive"))
    )
    (net (code "61") (name "Net-(T2-C)") (class "Default")
      (node (ref "R20") (pin "2") (pinfunction "2_2") (pintype "passive"))
      (node (ref "T2") (pin "3") (pinfunction "C_3") (pintype "passive"))
    )
    (net (code "62") (name "Net-(T3-B)") (class "Default")
      (node (ref "R3") (pin "1") (pinfunction "1_1") (pintype "passive"))
      (node (ref "R9") (pin "2") (pinfunction "2_2") (pintype "passive"))
      (node (ref "T3") (pin "1") (pinfunction "B_1") (pintype "passive"))
    )
    (net (code "63") (name "Net-(T3-C)") (class "Default")
      (node (ref "R21") (pin "2") (pinfunction "2_2") (pintype "passive"))
      (node (ref "T3") (pin "3") (pinfunction "C_3") (pintype "passive"))
    )
    (net (code "64") (name "Net-(T4-B)") (class "Default")
      (node (ref "R10") (pin "2") (pinfunction "2_2") (pintype "passive"))
      (node (ref "R4") (pin "1") (pinfunction "1_1") (pintype "passive"))
      (node (ref "T4") (pin "1") (pinfunction "B_1") (pintype "passive"))
    )
    (net (code "65") (name "Net-(T4-C)") (class "Default")
      (node (ref "R22") (pin "2") (pinfunction "2_2") (pintype "passive"))
      (node (ref "T4") (pin "3") (pinfunction "C_3") (pintype "passive"))
    )
    (net (code "66") (name "Net-(T5-B)") (class "Default")
      (node (ref "R11") (pin "2") (pinfunction "2_2") (pintype "passive"))
      (node (ref "R5") (pin "1") (pinfunction "1_1") (pintype "passive"))
      (node (ref "T5") (pin "1") (pinfunction "B_1") (pintype "passive"))
    )
    (net (code "67") (name "Net-(T5-C)") (class "Default")
      (node (ref "R23") (pin "2") (pinfunction "2_2") (pintype "passive"))
      (node (ref "T5") (pin "3") (pinfunction "C_3") (pintype "passive"))
    )
    (net (code "68") (name "Net-(T6-B)") (class "Default")
      (node (ref "R12") (pin "2") (pinfunction "2_2") (pintype "passive"))
      (node (ref "R6") (pin "1") (pinfunction "1_1") (pintype "passive"))
      (node (ref "T6") (pin "1") (pinfunction "B_1") (pintype "passive"))
    )
    (net (code "69") (name "Net-(T6-C)") (class "Default")
      (node (ref "R24") (pin "2") (pinfunction "2_2") (pintype "passive"))
      (node (ref "T6") (pin "3") (pinfunction "C_3") (pintype "passive"))
    )
    (net (code "70") (name "Net-(T7-B)") (class "Default")
      (node (ref "R13") (pin "2") (pinfunction "2_2") (pintype "passive"))
      (node (ref "R25") (pin "2") (pinfunction "2_2") (pintype "passive"))
      (node (ref "T7") (pin "1") (pinfunction "B_1") (pintype "passive"))
    )
    (net (code "71") (name "Net-(T7-C)") (class "Default")
      (node (ref "R7") (pin "1") (pinfunction "1_1") (pintype "passive"))
      (node (ref "T7") (pin "3") (pinfunction "C_3") (pintype "passive"))
    )
    (net (code "72") (name "Net-(T8-B)") (class "Default")
      (node (ref "R14") (pin "2") (pinfunction "2_2") (pintype "passive"))
      (node (ref "R26") (pin "2") (pinfunction "2_2") (pintype "passive"))
      (node (ref "T8") (pin "1") (pinfunction "B_1") (pintype "passive"))
    )
    (net (code "73") (name "Net-(T8-C)") (class "Default")
      (node (ref "R8") (pin "1") (pinfunction "1_1") (pintype "passive"))
      (node (ref "T8") (pin "3") (pinfunction "C_3") (pintype "passive"))
    )
    (net (code "74") (name "Net-(T9-B)") (class "Default")
      (node (ref "R15") (pin "2") (pinfunction "2_2") (pintype "passive"))
      (node (ref "R27") (pin "2") (pinfunction "2_2") (pintype "passive"))
      (node (ref "T9") (pin "1") (pinfunction "B_1") (pintype "passive"))
    )
    (net (code "75") (name "Net-(T9-C)") (class "Default")
      (node (ref "R9") (pin "1") (pinfunction "1_1") (pintype "passive"))
      (node (ref "T9") (pin "3") (pinfunction "C_3") (pintype "passive"))
    )
    (net (code "76") (name "Net-(T10-B)") (class "Default")
      (node (ref "R16") (pin "2") (pinfunction "2_2") (pintype "passive"))
      (node (ref "R28") (pin "2") (pinfunction "2_2") (pintype "passive"))
      (node (ref "T10") (pin "1") (pinfunction "B_1") (pintype "passive"))
    )
    (net (code "77") (name "Net-(T10-C)") (class "Default")
      (node (ref "R10") (pin "1") (pinfunction "1_1") (pintype "passive"))
      (node (ref "T10") (pin "3") (pinfunction "C_3") (pintype "passive"))
    )
    (net (code "78") (name "Net-(T11-B)") (class "Default")
      (node (ref "R17") (pin "2") (pinfunction "2_2") (pintype "passive"))
      (node (ref "R29") (pin "2") (pinfunction "2_2") (pintype "passive"))
      (node (ref "T11") (pin "1") (pinfunction "B_1") (pintype "passive"))
    )
    (net (code "79") (name "Net-(T11-C)") (class "Default")
      (node (ref "R11") (pin "1") (pinfunction "1_1") (pintype "passive"))
      (node (ref "T11") (pin "3") (pinfunction "C_3") (pintype "passive"))
    )
    (net (code "80") (name "Net-(T12-B)") (class "Default")
      (node (ref "R18") (pin "2") (pinfunction "2_2") (pintype "passive"))
      (node (ref "R30") (pin "2") (pinfunction "2_2") (pintype "passive"))
      (node (ref "T12") (pin "1") (pinfunction "B_1") (pintype "passive"))
    )
    (net (code "81") (name "Net-(T12-C)") (class "Default")
      (node (ref "R12") (pin "1") (pinfunction "1_1") (pintype "passive"))
      (node (ref "T12") (pin "3") (pinfunction "C_3") (pintype "passive"))
    )
    (net (code "82") (name "Net-(T13-B)") (class "Default")
      (node (ref "R31") (pin "2") (pinfunction "2_2") (pintype "passive"))
      (node (ref "R41") (pin "2") (pinfunction "2_2") (pintype "passive"))
      (node (ref "T13") (pin "1") (pinfunction "B_1") (pintype "passive"))
    )
    (net (code "83") (name "Net-(T14-B)") (class "Default")
      (node (ref "R32") (pin "2") (pinfunction "2_2") (pintype "passive"))
      (node (ref "R42") (pin "2") (pinfunction "2_2") (pintype "passive"))
      (node (ref "T14") (pin "1") (pinfunction "B_1") (pintype "passive"))
    )
    (net (code "84") (name "Net-(T15-B)") (class "Default")
      (node (ref "R33") (pin "2") (pinfunction "2_2") (pintype "passive"))
      (node (ref "R43") (pin "2") (pinfunction "2_2") (pintype "passive"))
      (node (ref "T15") (pin "1") (pinfunction "B_1") (pintype "passive"))
    )
    (net (code "85") (name "Net-(T16-B)") (class "Default")
      (node (ref "R34") (pin "2") (pinfunction "2_2") (pintype "passive"))
      (node (ref "R44") (pin "2") (pinfunction "2_2") (pintype "passive"))
      (node (ref "T16") (pin "1") (pinfunction "B_1") (pintype "passive"))
    )
    (net (code "86") (name "Net-(T17-B)") (class "Default")
      (node (ref "R35") (pin "2") (pinfunction "2_2") (pintype "passive"))
      (node (ref "R45") (pin "2") (pinfunction "2_2") (pintype "passive"))
      (node (ref "T17") (pin "1") (pinfunction "B_1") (pintype "passive"))
    )
    (net (code "87") (name "Net-(T18-B)") (class "Default")
      (node (ref "R36") (pin "2") (pinfunction "2_2") (pintype "passive"))
      (node (ref "R46") (pin "2") (pinfunction "2_2") (pintype "passive"))
      (node (ref "T18") (pin "1") (pinfunction "B_1") (pintype "passive"))
    )
    (net (code "88") (name "Net-(T19-B)") (class "Default")
      (node (ref "R37") (pin "2") (pinfunction "2_2") (pintype "passive"))
      (node (ref "R47") (pin "2") (pinfunction "2_2") (pintype "passive"))
      (node (ref "T19") (pin "1") (pinfunction "B_1") (pintype "passive"))
    )
    (net (code "89") (name "Net-(T20-B)") (class "Default")
      (node (ref "R38") (pin "2") (pinfunction "2_2") (pintype "passive"))
      (node (ref "R48") (pin "2") (pinfunction "2_2") (pintype "passive"))
      (node (ref "T20") (pin "1") (pinfunction "B_1") (pintype "passive"))
    )
    (net (code "90") (name "Net-(T21-B)") (class "Default")
      (node (ref "R39") (pin "2") (pinfunction "2_2") (pintype "passive"))
      (node (ref "R49") (pin "2") (pinfunction "2_2") (pintype "passive"))
      (node (ref "T21") (pin "1") (pinfunction "B_1") (pintype "passive"))
    )
    (net (code "91") (name "Net-(T22-B)") (class "Default")
      (node (ref "R40") (pin "2") (pinfunction "2_2") (pintype "passive"))
      (node (ref "R50") (pin "2") (pinfunction "2_2") (pintype "passive"))
      (node (ref "T22") (pin "1") (pinfunction "B_1") (pintype "passive"))
    )
    (net (code "92") (name "Net-(T23-B)") (class "Default")
      (node (ref "R59") (pin "2") (pinfunction "2_2") (pintype "passive"))
      (node (ref "R67") (pin "2") (pinfunction "2_2") (pintype "passive"))
      (node (ref "T23") (pin "1") (pinfunction "B_1") (pintype "passive"))
    )
    (net (code "93") (name "Net-(T24-B)") (class "Default")
      (node (ref "R60") (pin "2") (pinfunction "2_2") (pintype "passive"))
      (node (ref "R68") (pin "2") (pinfunction "2_2") (pintype "passive"))
      (node (ref "T24") (pin "1") (pinfunction "B_1") (pintype "passive"))
    )
    (net (code "94") (name "Net-(T25-B)") (class "Default")
      (node (ref "R61") (pin "2") (pinfunction "2_2") (pintype "passive"))
      (node (ref "R69") (pin "2") (pinfunction "2_2") (pintype "passive"))
      (node (ref "T25") (pin "1") (pinfunction "B_1") (pintype "passive"))
    )
    (net (code "95") (name "Net-(T26-B)") (class "Default")
      (node (ref "R62") (pin "2") (pinfunction "2_2") (pintype "passive"))
      (node (ref "R70") (pin "2") (pinfunction "2_2") (pintype "passive"))
      (node (ref "T26") (pin "1") (pinfunction "B_1") (pintype "passive"))
    )
    (net (code "96") (name "Net-(T27-B)") (class "Default")
      (node (ref "R63") (pin "2") (pinfunction "2_2") (pintype "passive"))
      (node (ref "R71") (pin "2") (pinfunction "2_2") (pintype "passive"))
      (node (ref "T27") (pin "1") (pinfunction "B_1") (pintype "passive"))
    )
    (net (code "97") (name "Net-(T28-B)") (class "Default")
      (node (ref "R64") (pin "2") (pinfunction "2_2") (pintype "passive"))
      (node (ref "R72") (pin "2") (pinfunction "2_2") (pintype "passive"))
      (node (ref "T28") (pin "1") (pinfunction "B_1") (pintype "passive"))
    )
    (net (code "98") (name "Net-(T29-B)") (class "Default")
      (node (ref "R65") (pin "2") (pinfunction "2_2") (pintype "passive"))
      (node (ref "R73") (pin "2") (pinfunction "2_2") (pintype "passive"))
      (node (ref "T29") (pin "1") (pinfunction "B_1") (pintype "passive"))
    )
    (net (code "99") (name "Net-(T29-C)") (class "Default")
      (node (ref "R57") (pin "1") (pinfunction "1_1") (pintype "passive"))
      (node (ref "T29") (pin "3") (pinfunction "C_3") (pintype "passive"))
    )
    (net (code "100") (name "Net-(T30-B)") (class "Default")
      (node (ref "R66") (pin "2") (pinfunction "2_2") (pintype "passive"))
      (node (ref "R74") (pin "2") (pinfunction "2_2") (pintype "passive"))
      (node (ref "T30") (pin "1") (pinfunction "B_1") (pintype "passive"))
    )
    (net (code "101") (name "Net-(T30-C)") (class "Default")
      (node (ref "R58") (pin "1") (pinfunction "1_1") (pintype "passive"))
      (node (ref "T30") (pin "3") (pinfunction "C_3") (pintype "passive"))
    )
    (net (code "102") (name "unconnected-(J4-Pad2)") (class "Default")
      (node (ref "J4") (pin "2") (pinfunction "2_2") (pintype "passive+no_connect"))
    )
    (net (code "103") (name "unconnected-(V1-PL-Pad2)") (class "Default")
      (node (ref "V1") (pin "2") (pinfunction "PL_2") (pintype "passive+no_connect"))
    )
    (net (code "104") (name "unconnected-(V1-PR-Pad13)") (class "Default")
      (node (ref "V1") (pin "13") (pinfunction "PR_13") (pintype "passive+no_connect"))
    )
    (net (code "105") (name "unconnected-(V2-PL-Pad2)") (class "Default")
      (node (ref "V2") (pin "2") (pinfunction "PL_2") (pintype "passive+no_connect"))
    )
    (net (code "106") (name "unconnected-(V2-PR-Pad13)") (class "Default")
      (node (ref "V2") (pin "13") (pinfunction "PR_13") (pintype "passive+no_connect"))
    )
    (net (code "107") (name "unconnected-(V3-PL-Pad2)") (class "Default")
      (node (ref "V3") (pin "2") (pinfunction "PL_2") (pintype "passive+no_connect"))
    )
    (net (code "108") (name "unconnected-(V3-PR-Pad13)") (class "Default")
      (node (ref "V3") (pin "13") (pinfunction "PR_13") (pintype "passive+no_connect"))
    )
    (net (code "109") (name "unconnected-(V4-PL-Pad2)") (class "Default")
      (node (ref "V4") (pin "2") (pinfunction "PL_2") (pintype "passive+no_connect"))
    )
    (net (code "110") (name "unconnected-(V4-PR-Pad13)") (class "Default")
      (node (ref "V4") (pin "13") (pinfunction "PR_13") (pintype "passive+no_connect"))
    )
    (net (code "111") (name "unconnected-(V5-PL-Pad2)") (class "Default")
      (node (ref "V5") (pin "2") (pinfunction "PL_2") (pintype "passive+no_connect"))
    )
    (net (code "112") (name "unconnected-(V5-PR-Pad13)") (class "Default")
      (node (ref "V5") (pin "13") (pinfunction "PR_13") (pintype "passive+no_connect"))
    )
    (net (code "113") (name "unconnected-(V6-PL-Pad2)") (class "Default")
      (node (ref "V6") (pin "2") (pinfunction "PL_2") (pintype "passive+no_connect"))
    )
    (net (code "114") (name "unconnected-(V6-PR-Pad13)") (class "Default")
      (node (ref "V6") (pin "13") (pinfunction "PR_13") (pintype "passive+no_connect"))
    )
  )
)
